# stages_v70.net
KiCad netlist of a schematic drawn in EAGLE
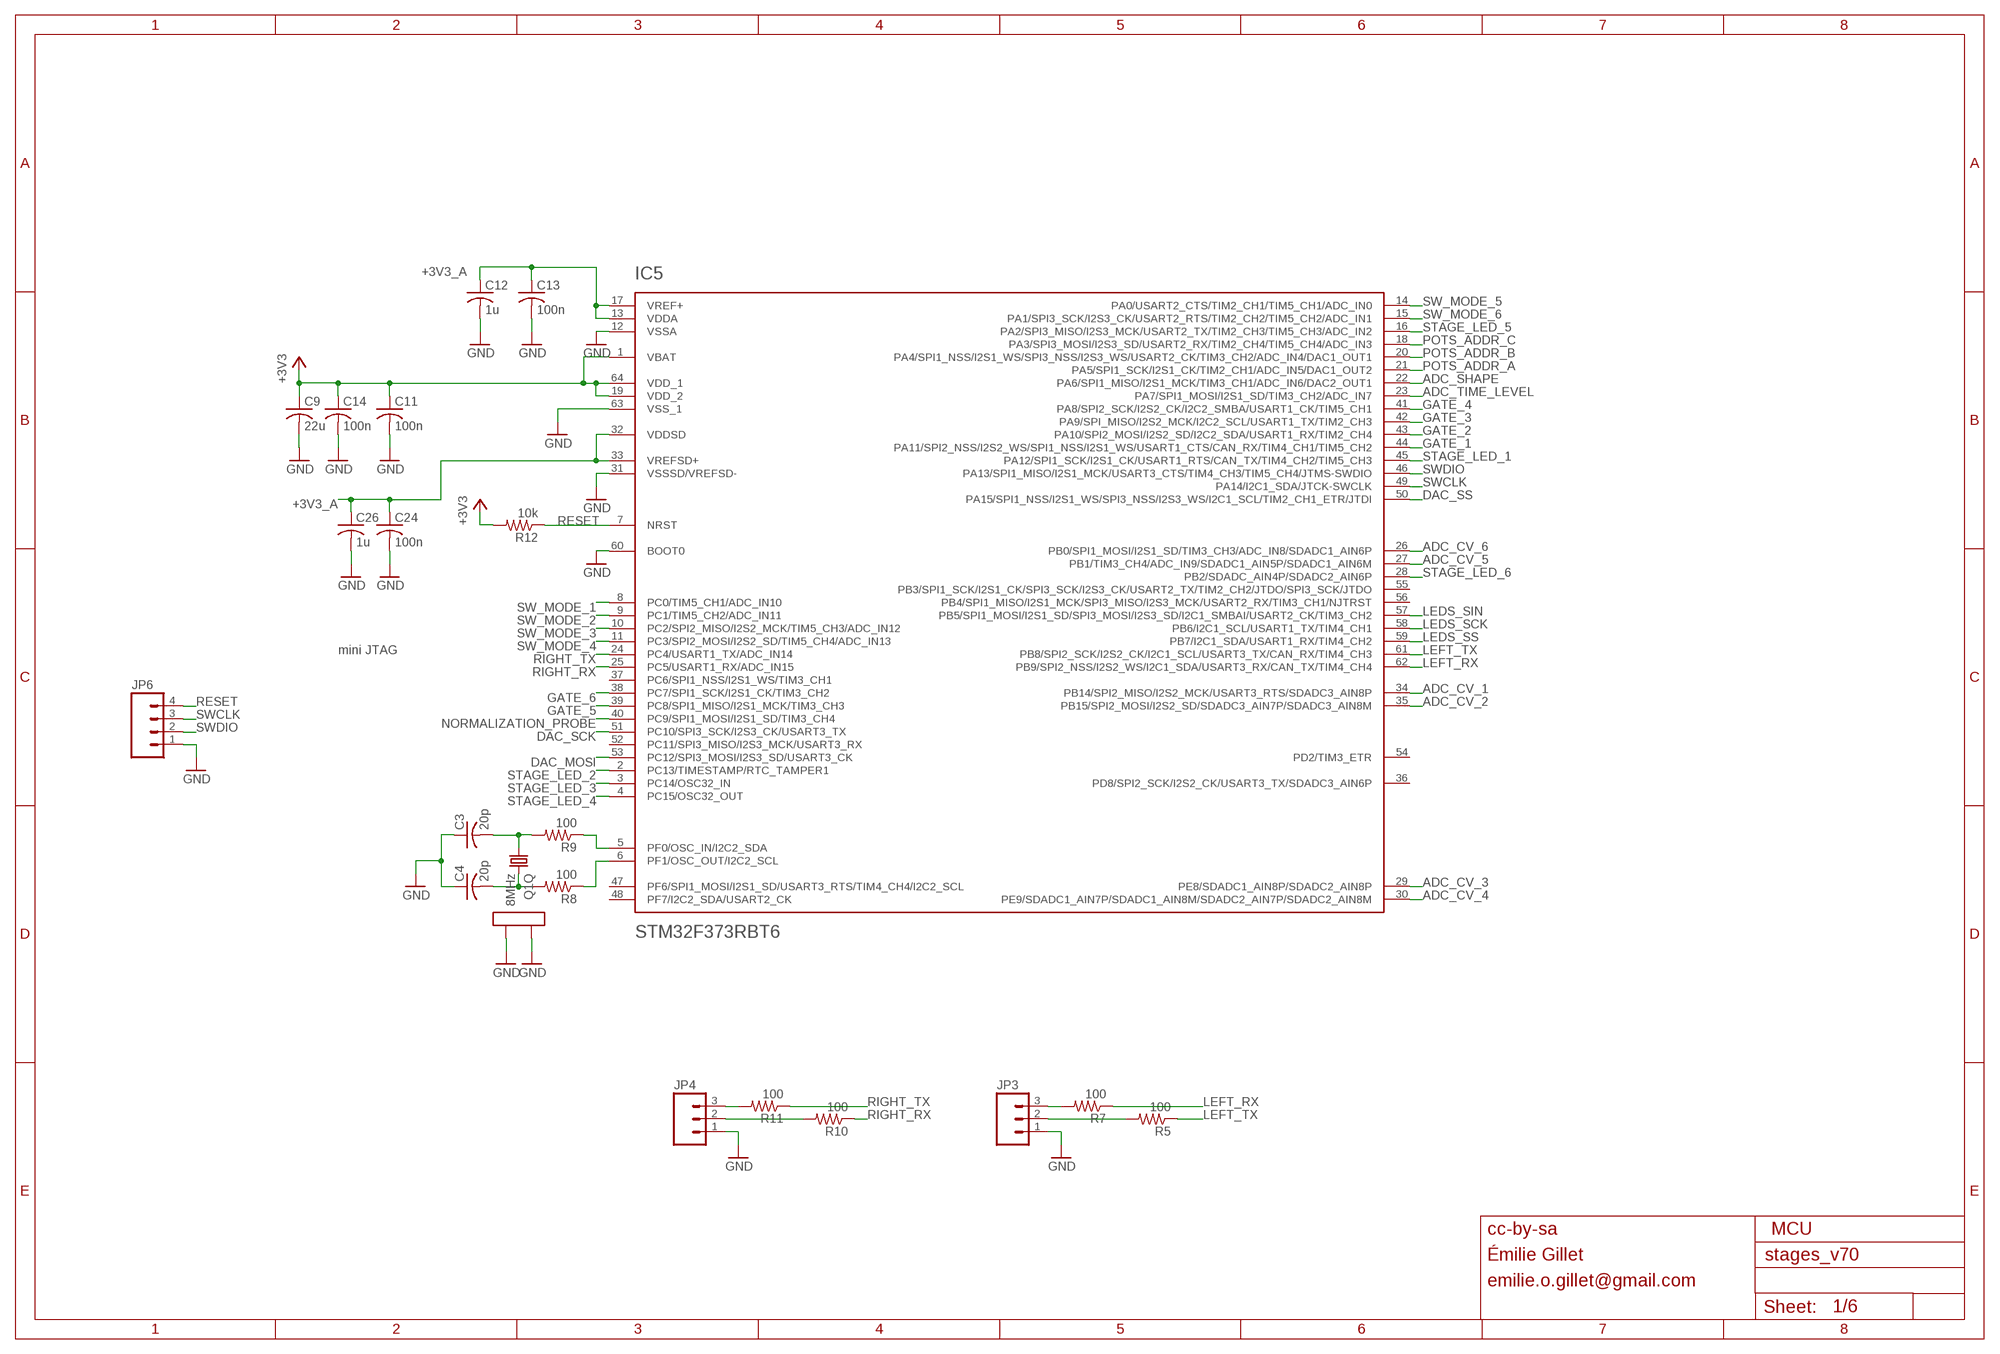
[diagram p0: schematic, sheet 1]
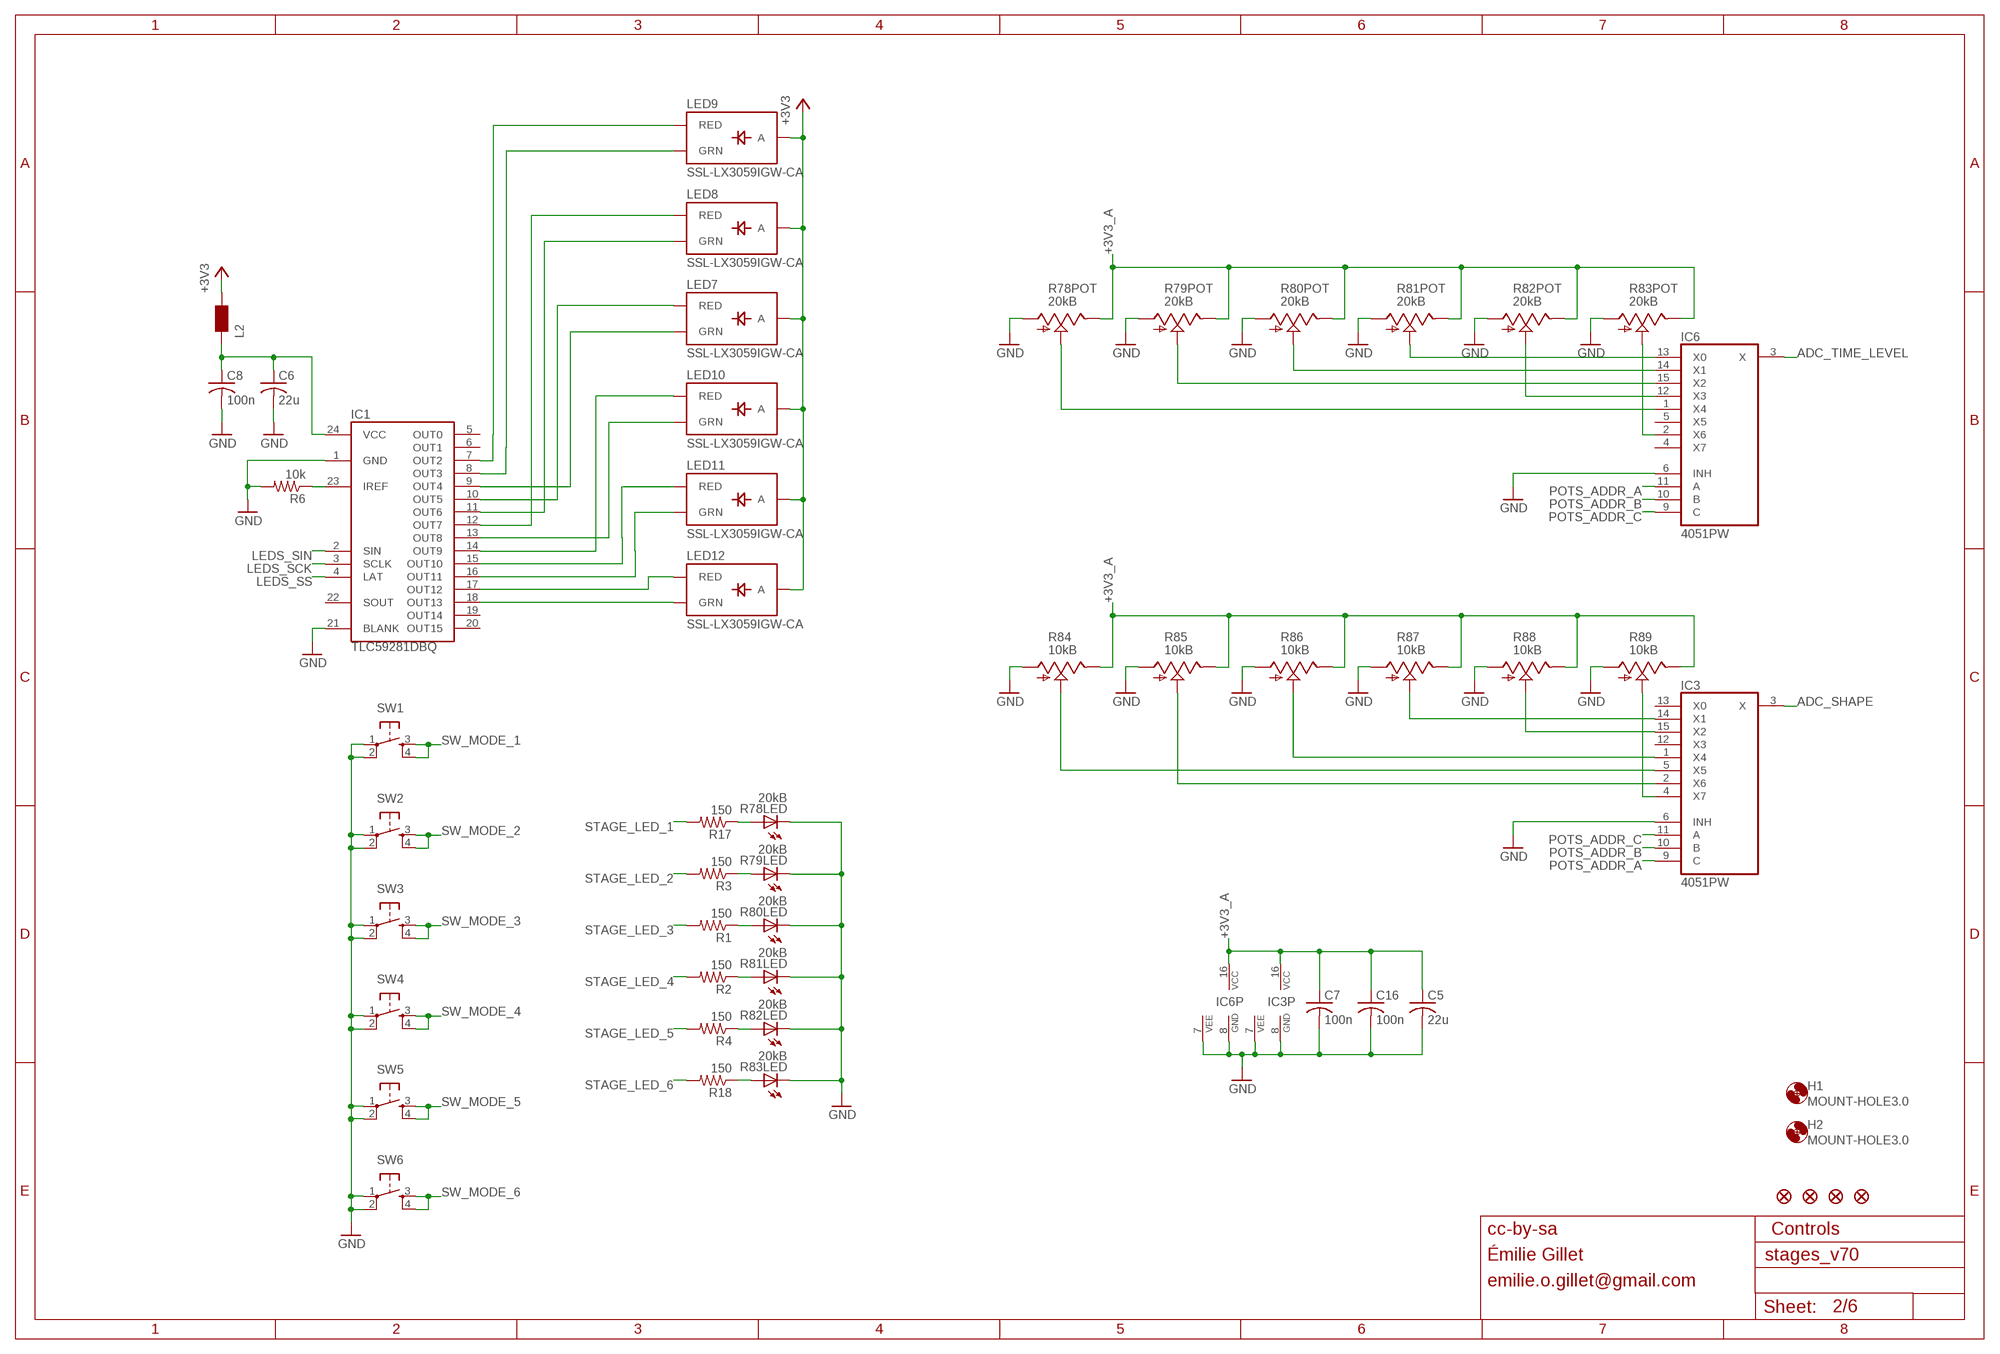
[diagram p1: schematic, sheet 2]
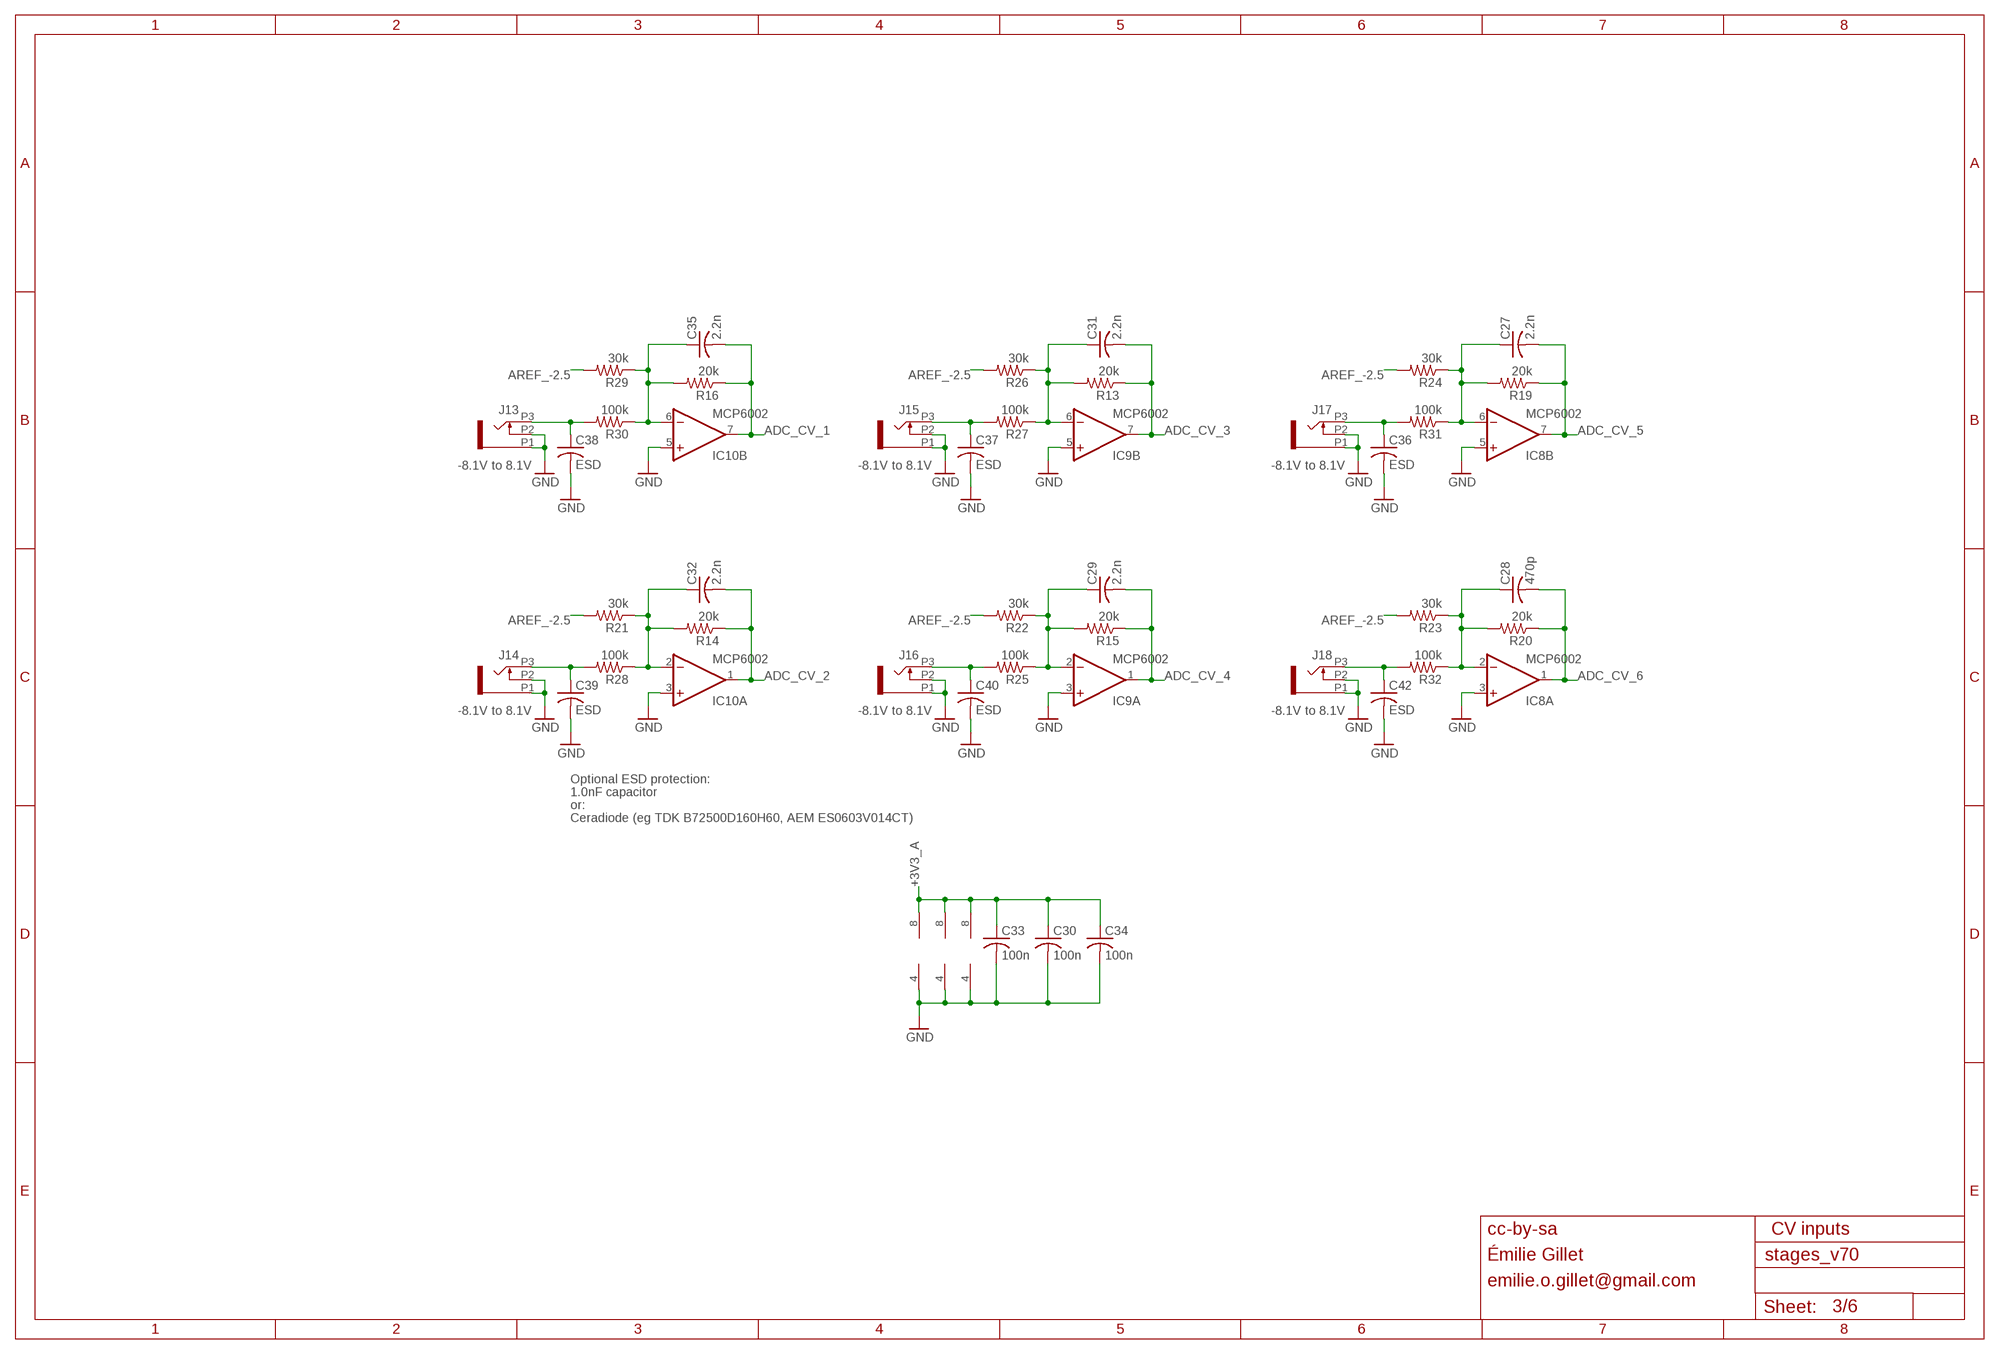
[diagram p2: schematic, sheet 3]
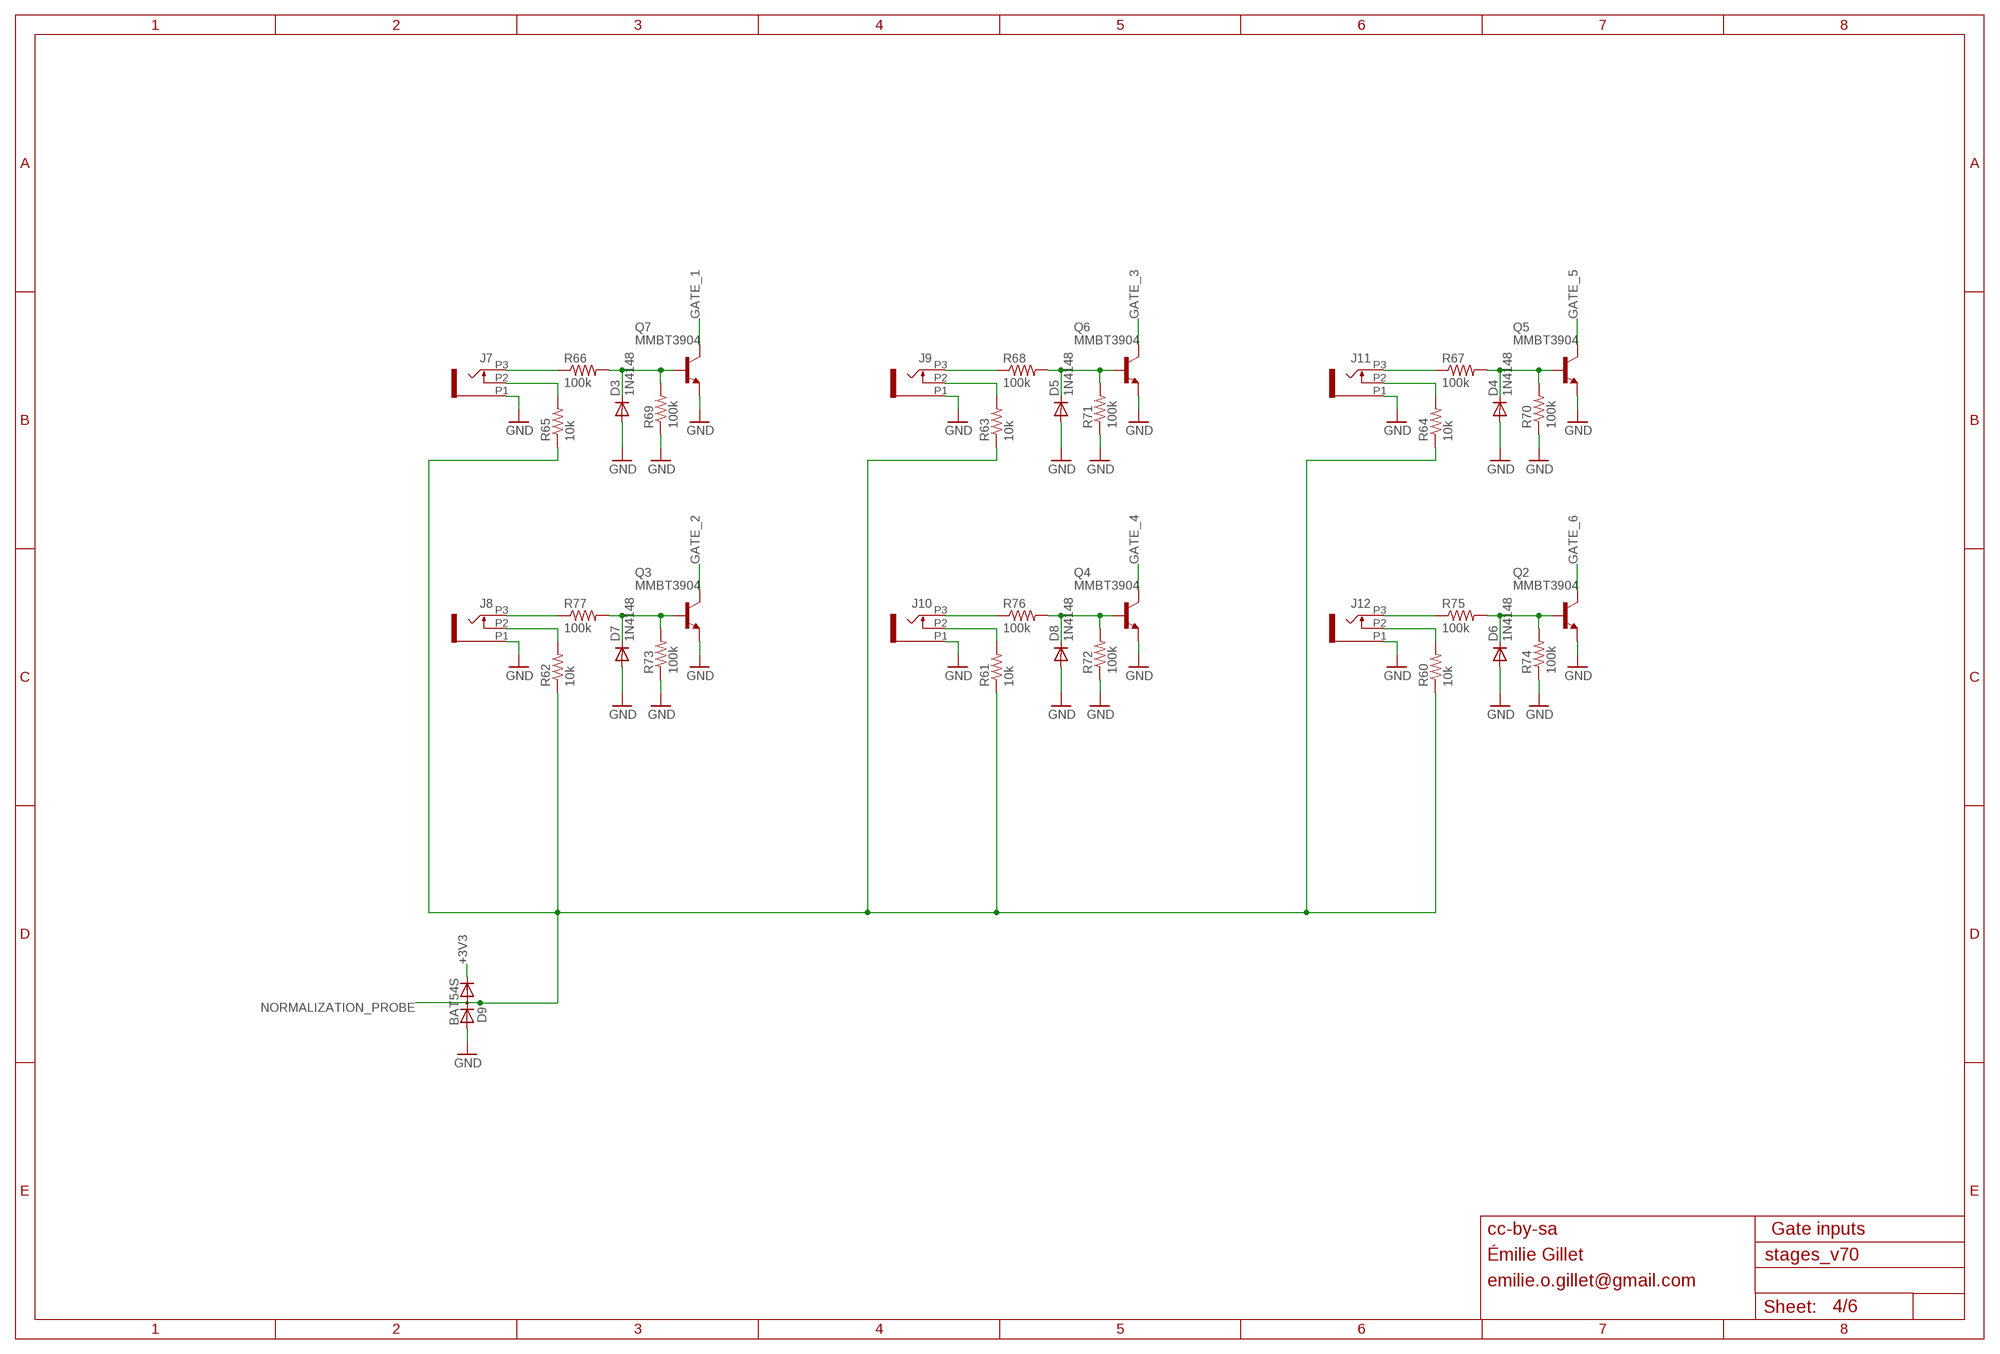
[diagram p3: schematic, sheet 4]
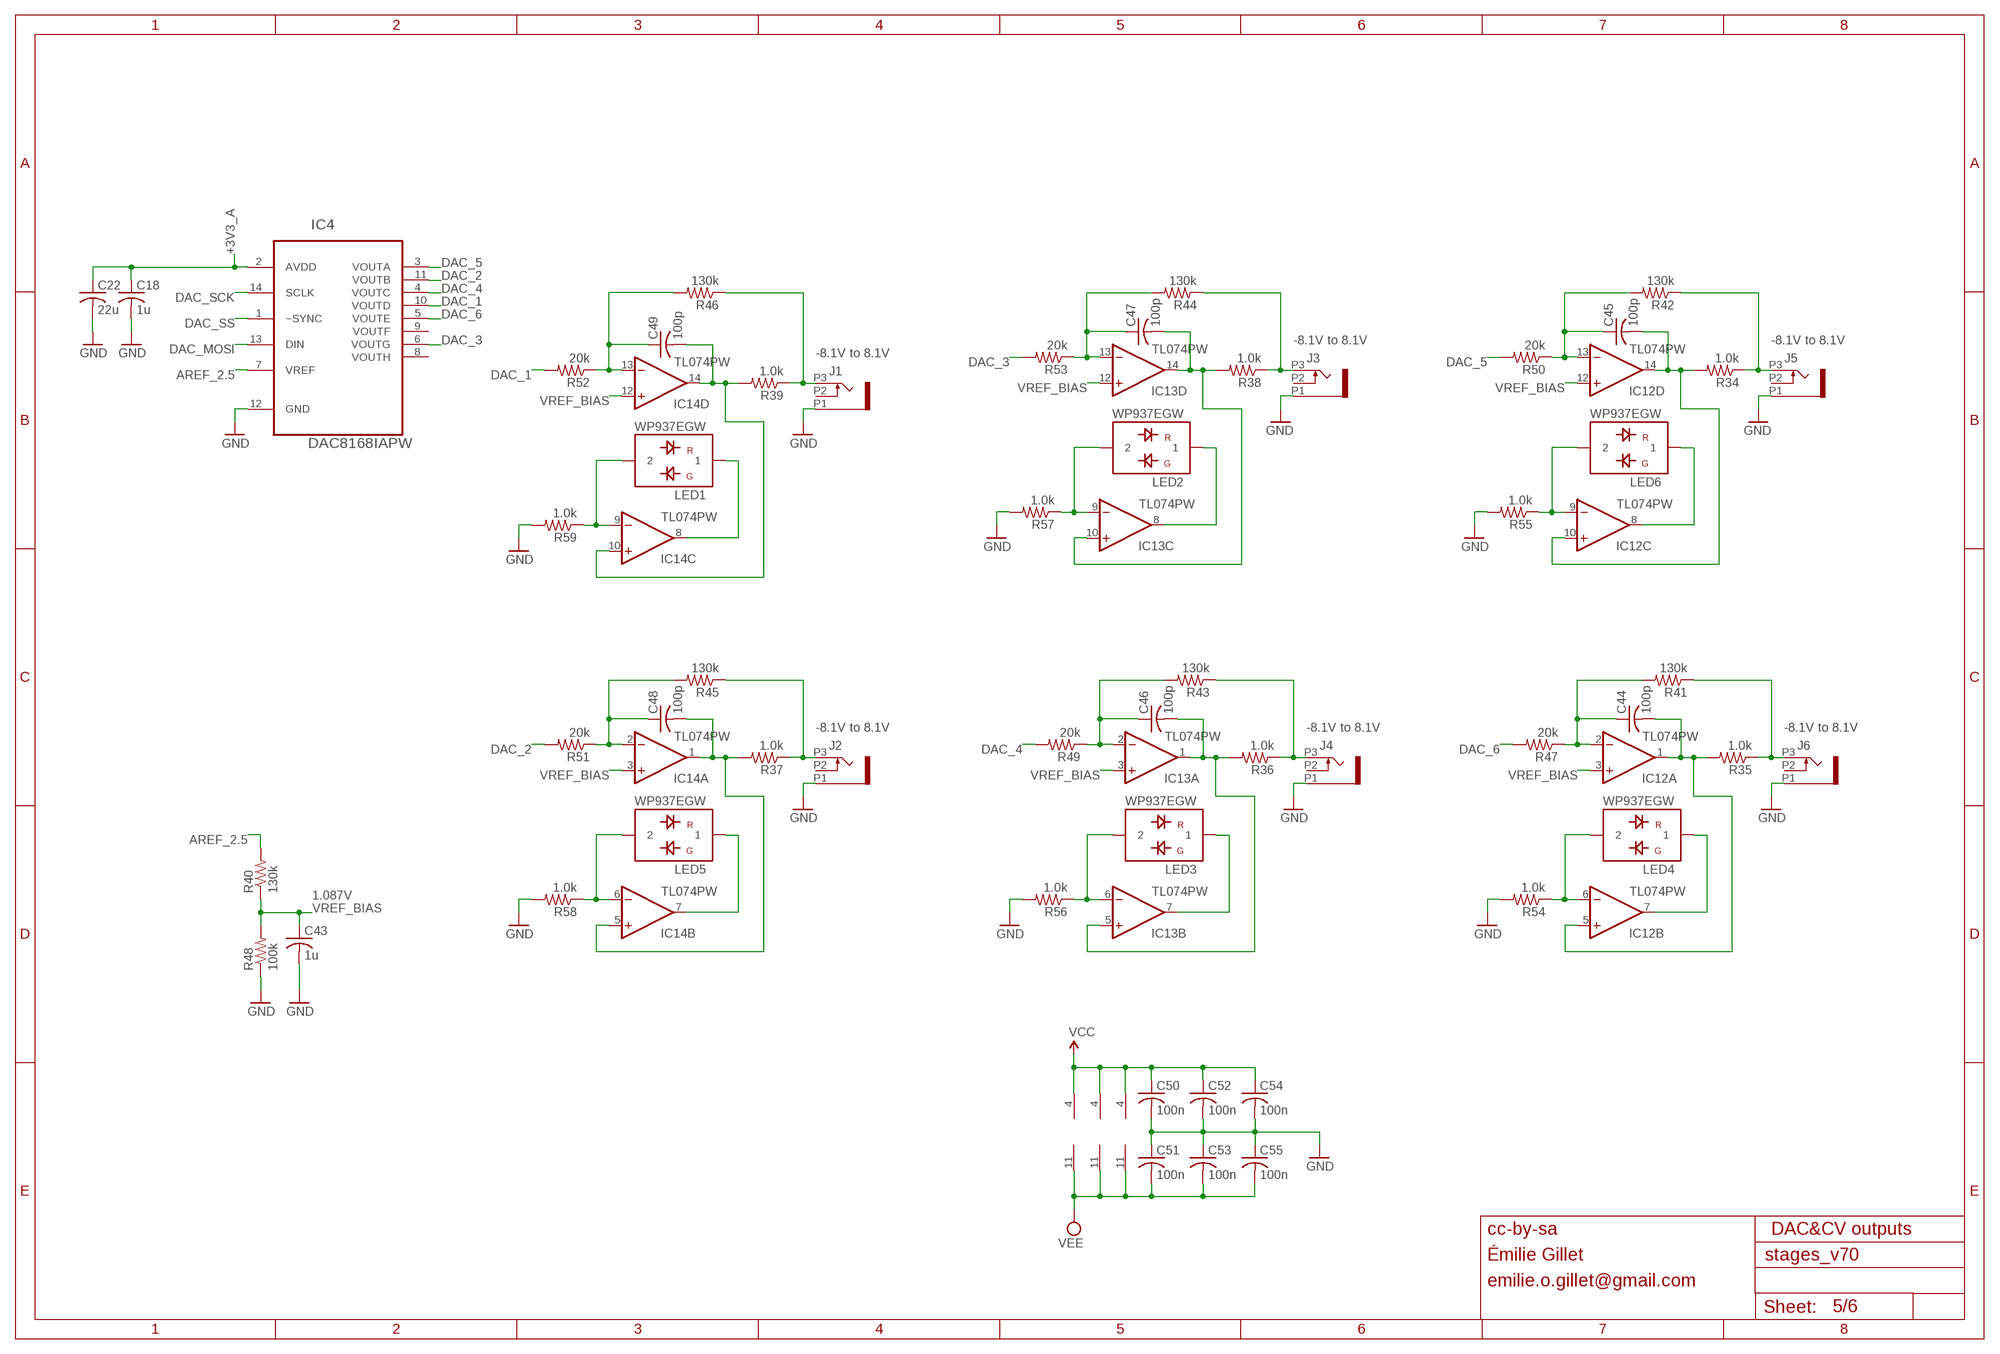
[diagram p4: schematic, sheet 5]
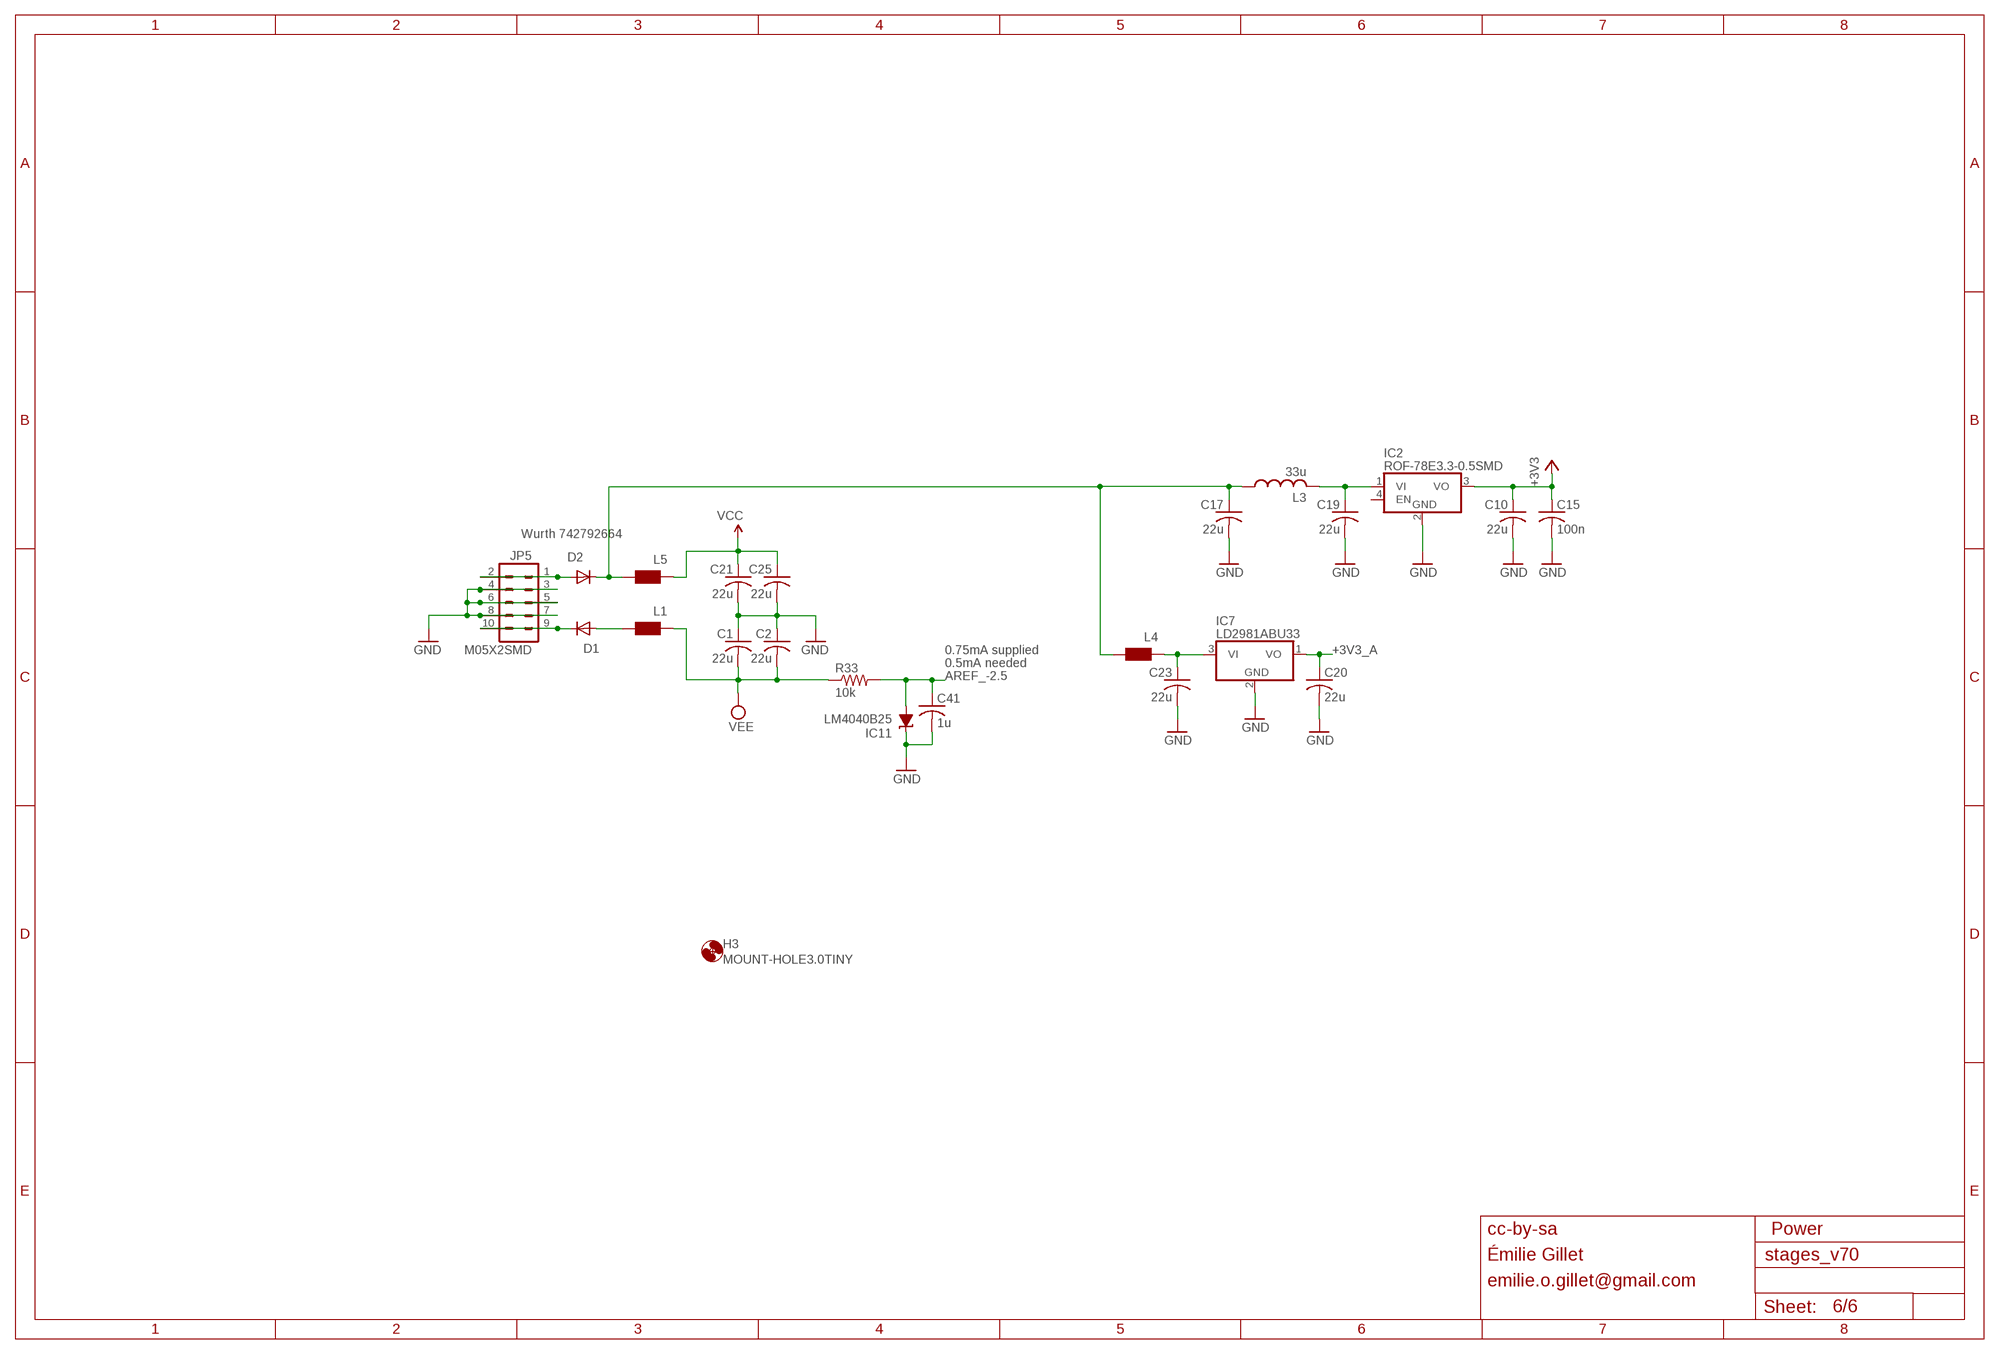
[diagram p5: schematic, sheet 6]

(export (version "E")
  (design (tool "Eeschema 10.0.6"))
  (components
    (comp (ref "C27")
      (value "2.2n")
      (footprint "eagle-import:C0402")
      (libsource (lib "eagle-import") (part "C-USC0402"))
    )
    (comp (ref "C28")
      (value "470p")
      (footprint "eagle-import:C0402")
      (libsource (lib "eagle-import") (part "C-USC0402"))
    )
    (comp (ref "C29")
      (value "2.2n")
      (footprint "eagle-import:C0402")
      (libsource (lib "eagle-import") (part "C-USC0402"))
    )
    (comp (ref "C30")
      (value "100n")
      (footprint "eagle-import:C0402")
      (libsource (lib "eagle-import") (part "C-USC0402"))
    )
    (comp (ref "C31")
      (value "2.2n")
      (footprint "eagle-import:C0402")
      (libsource (lib "eagle-import") (part "C-USC0402"))
    )
    (comp (ref "C32")
      (value "2.2n")
      (footprint "eagle-import:C0402")
      (libsource (lib "eagle-import") (part "C-USC0402"))
    )
    (comp (ref "C33")
      (value "100n")
      (footprint "eagle-import:C0402")
      (libsource (lib "eagle-import") (part "C-USC0402"))
    )
    (comp (ref "C34")
      (value "100n")
      (footprint "eagle-import:C0402")
      (libsource (lib "eagle-import") (part "C-USC0402"))
    )
    (comp (ref "C35")
      (value "2.2n")
      (footprint "eagle-import:C0402")
      (libsource (lib "eagle-import") (part "C-USC0402"))
    )
    (comp (ref "C36")
      (value "ESD")
      (footprint "eagle-import:C0603")
      (libsource (lib "eagle-import") (part "C-USC0603"))
    )
    (comp (ref "C37")
      (value "ESD")
      (footprint "eagle-import:C0603")
      (libsource (lib "eagle-import") (part "C-USC0603"))
    )
    (comp (ref "C38")
      (value "ESD")
      (footprint "eagle-import:C0603")
      (libsource (lib "eagle-import") (part "C-USC0603"))
    )
    (comp (ref "C39")
      (value "ESD")
      (footprint "eagle-import:C0603")
      (libsource (lib "eagle-import") (part "C-USC0603"))
    )
    (comp (ref "C40")
      (value "ESD")
      (footprint "eagle-import:C0603")
      (libsource (lib "eagle-import") (part "C-USC0603"))
    )
    (comp (ref "C42")
      (value "ESD")
      (footprint "eagle-import:C0603")
      (libsource (lib "eagle-import") (part "C-USC0603"))
    )
    (comp (ref "IC8")
      (value "MCP6002")
      (footprint "eagle-import:MSOP-8")
      (libsource (lib "eagle-import") (part "OPA1652DGK"))
    )
    (comp (ref "IC9")
      (value "MCP6002")
      (footprint "eagle-import:MSOP-8")
      (libsource (lib "eagle-import") (part "OPA1652DGK"))
    )
    (comp (ref "IC10")
      (value "MCP6002")
      (footprint "eagle-import:MSOP-8")
      (libsource (lib "eagle-import") (part "OPA1652DGK"))
    )
    (comp (ref "J13")
      (value "PJ301_THONKICONN6")
      (footprint "eagle-import:WQP_PJ_301M6")
      (libsource (lib "eagle-import") (part "PJ301_THONKICONN6"))
    )
    (comp (ref "J14")
      (value "PJ301_THONKICONN6")
      (footprint "eagle-import:WQP_PJ_301M6")
      (libsource (lib "eagle-import") (part "PJ301_THONKICONN6"))
    )
    (comp (ref "J15")
      (value "PJ301_THONKICONN6")
      (footprint "eagle-import:WQP_PJ_301M6")
      (libsource (lib "eagle-import") (part "PJ301_THONKICONN6"))
    )
    (comp (ref "J16")
      (value "PJ301_THONKICONN6")
      (footprint "eagle-import:WQP_PJ_301M6")
      (libsource (lib "eagle-import") (part "PJ301_THONKICONN6"))
    )
    (comp (ref "J17")
      (value "PJ301_THONKICONN6")
      (footprint "eagle-import:WQP_PJ_301M6")
      (libsource (lib "eagle-import") (part "PJ301_THONKICONN6"))
    )
    (comp (ref "J18")
      (value "PJ301_THONKICONN6")
      (footprint "eagle-import:WQP_PJ_301M6")
      (libsource (lib "eagle-import") (part "PJ301_THONKICONN6"))
    )
    (comp (ref "R13")
      (value "20k")
      (footprint "eagle-import:R0402")
      (libsource (lib "eagle-import") (part "R-US_R0402"))
    )
    (comp (ref "R14")
      (value "20k")
      (footprint "eagle-import:R0402")
      (libsource (lib "eagle-import") (part "R-US_R0402"))
    )
    (comp (ref "R15")
      (value "20k")
      (footprint "eagle-import:R0402")
      (libsource (lib "eagle-import") (part "R-US_R0402"))
    )
    (comp (ref "R16")
      (value "20k")
      (footprint "eagle-import:R0402")
      (libsource (lib "eagle-import") (part "R-US_R0402"))
    )
    (comp (ref "R19")
      (value "20k")
      (footprint "eagle-import:R0402")
      (libsource (lib "eagle-import") (part "R-US_R0402"))
    )
    (comp (ref "R20")
      (value "20k")
      (footprint "eagle-import:R0402")
      (libsource (lib "eagle-import") (part "R-US_R0402"))
    )
    (comp (ref "R21")
      (value "30k")
      (footprint "eagle-import:R0402")
      (libsource (lib "eagle-import") (part "R-US_R0402"))
    )
    (comp (ref "R22")
      (value "30k")
      (footprint "eagle-import:R0402")
      (libsource (lib "eagle-import") (part "R-US_R0402"))
    )
    (comp (ref "R23")
      (value "30k")
      (footprint "eagle-import:R0402")
      (libsource (lib "eagle-import") (part "R-US_R0402"))
    )
    (comp (ref "R24")
      (value "30k")
      (footprint "eagle-import:R0402")
      (libsource (lib "eagle-import") (part "R-US_R0402"))
    )
    (comp (ref "R25")
      (value "100k")
      (footprint "eagle-import:R0402")
      (libsource (lib "eagle-import") (part "R-US_R0402"))
    )
    (comp (ref "R26")
      (value "30k")
      (footprint "eagle-import:R0402")
      (libsource (lib "eagle-import") (part "R-US_R0402"))
    )
    (comp (ref "R27")
      (value "100k")
      (footprint "eagle-import:R0402")
      (libsource (lib "eagle-import") (part "R-US_R0402"))
    )
    (comp (ref "R28")
      (value "100k")
      (footprint "eagle-import:R0402")
      (libsource (lib "eagle-import") (part "R-US_R0402"))
    )
    (comp (ref "R29")
      (value "30k")
      (footprint "eagle-import:R0402")
      (libsource (lib "eagle-import") (part "R-US_R0402"))
    )
    (comp (ref "R30")
      (value "100k")
      (footprint "eagle-import:R0402")
      (libsource (lib "eagle-import") (part "R-US_R0402"))
    )
    (comp (ref "R31")
      (value "100k")
      (footprint "eagle-import:R0402")
      (libsource (lib "eagle-import") (part "R-US_R0402"))
    )
    (comp (ref "R32")
      (value "100k")
      (footprint "eagle-import:R0402")
      (libsource (lib "eagle-import") (part "R-US_R0402"))
    )
    (comp (ref "C5")
      (value "22u")
      (footprint "eagle-import:C1206")
      (libsource (lib "eagle-import") (part "C-USC1206"))
    )
    (comp (ref "C6")
      (value "22u")
      (footprint "eagle-import:C1206")
      (libsource (lib "eagle-import") (part "C-USC1206"))
    )
    (comp (ref "C7")
      (value "100n")
      (footprint "eagle-import:C0402")
      (libsource (lib "eagle-import") (part "C-USC0402"))
    )
    (comp (ref "C8")
      (value "100n")
      (footprint "eagle-import:C0402")
      (libsource (lib "eagle-import") (part "C-USC0402"))
    )
    (comp (ref "C16")
      (value "100n")
      (footprint "eagle-import:C0402")
      (libsource (lib "eagle-import") (part "C-USC0402"))
    )
    (comp (ref "H1")
      (value "MOUNT-HOLE3.0")
      (footprint "eagle-import:3,0")
      (libsource (lib "eagle-import") (part "MOUNT-HOLE3.0"))
    )
    (comp (ref "H2")
      (value "MOUNT-HOLE3.0")
      (footprint "eagle-import:3,0")
      (libsource (lib "eagle-import") (part "MOUNT-HOLE3.0"))
    )
    (comp (ref "IC1")
      (value "TLC59281DBQ")
      (footprint "eagle-import:TSSOP24_0635")
      (libsource (lib "eagle-import") (part "TLC59281DBQ"))
    )
    (comp (ref "IC3")
      (value "4051PW")
      (footprint "eagle-import:TSSOP16_065")
      (libsource (lib "eagle-import") (part "4051PW"))
    )
    (comp (ref "IC6")
      (value "4051PW")
      (footprint "eagle-import:TSSOP16_065")
      (libsource (lib "eagle-import") (part "4051PW"))
    )
    (comp (ref "JP1")
      (value "FIDUCIAL1X2")
      (footprint "eagle-import:FIDUCIAL-1X2")
      (libsource (lib "eagle-import") (part "FIDUCIAL1X2"))
    )
    (comp (ref "JP2")
      (value "FIDUCIAL1X2")
      (footprint "eagle-import:FIDUCIAL-1X2")
      (libsource (lib "eagle-import") (part "FIDUCIAL1X2"))
    )
    (comp (ref "JP7")
      (value "FIDUCIAL1X2")
      (footprint "eagle-import:FIDUCIAL-1X2")
      (libsource (lib "eagle-import") (part "FIDUCIAL1X2"))
    )
    (comp (ref "JP8")
      (value "FIDUCIAL1X2")
      (footprint "eagle-import:FIDUCIAL-1X2")
      (libsource (lib "eagle-import") (part "FIDUCIAL1X2"))
    )
    (comp (ref "L2")
      (value "WE-CBF_0603")
      (footprint "eagle-import:0603")
      (libsource (lib "eagle-import") (part "WE-CBF_0603"))
    )
    (comp (ref "LED7")
      (value "SSL-LX3059IGW-CA")
      (footprint "eagle-import:LED-BICOLOR-THROUGHHOLE-LUMEX")
      (libsource (lib "eagle-import") (part "LED-BICOLOR-THROUGHHOLE-CA"))
    )
    (comp (ref "LED8")
      (value "SSL-LX3059IGW-CA")
      (footprint "eagle-import:LED-BICOLOR-THROUGHHOLE-LUMEX")
      (libsource (lib "eagle-import") (part "LED-BICOLOR-THROUGHHOLE-CA"))
    )
    (comp (ref "LED9")
      (value "SSL-LX3059IGW-CA")
      (footprint "eagle-import:LED-BICOLOR-THROUGHHOLE-LUMEX")
      (libsource (lib "eagle-import") (part "LED-BICOLOR-THROUGHHOLE-CA"))
    )
    (comp (ref "LED10")
      (value "SSL-LX3059IGW-CA")
      (footprint "eagle-import:LED-BICOLOR-THROUGHHOLE-LUMEX")
      (libsource (lib "eagle-import") (part "LED-BICOLOR-THROUGHHOLE-CA"))
    )
    (comp (ref "LED11")
      (value "SSL-LX3059IGW-CA")
      (footprint "eagle-import:LED-BICOLOR-THROUGHHOLE-LUMEX")
      (libsource (lib "eagle-import") (part "LED-BICOLOR-THROUGHHOLE-CA"))
    )
    (comp (ref "LED12")
      (value "SSL-LX3059IGW-CA")
      (footprint "eagle-import:LED-BICOLOR-THROUGHHOLE-LUMEX")
      (libsource (lib "eagle-import") (part "LED-BICOLOR-THROUGHHOLE-CA"))
    )
    (comp (ref "R1")
      (value "150")
      (footprint "eagle-import:R0402")
      (libsource (lib "eagle-import") (part "R-US_R0402"))
    )
    (comp (ref "R2")
      (value "150")
      (footprint "eagle-import:R0402")
      (libsource (lib "eagle-import") (part "R-US_R0402"))
    )
    (comp (ref "R3")
      (value "150")
      (footprint "eagle-import:R0402")
      (libsource (lib "eagle-import") (part "R-US_R0402"))
    )
    (comp (ref "R4")
      (value "150")
      (footprint "eagle-import:R0402")
      (libsource (lib "eagle-import") (part "R-US_R0402"))
    )
    (comp (ref "R6")
      (value "10k")
      (footprint "eagle-import:R0402")
      (libsource (lib "eagle-import") (part "R-US_R0402"))
    )
    (comp (ref "R17")
      (value "150")
      (footprint "eagle-import:R0402")
      (libsource (lib "eagle-import") (part "R-US_R0402"))
    )
    (comp (ref "R18")
      (value "150")
      (footprint "eagle-import:R0402")
      (libsource (lib "eagle-import") (part "R-US_R0402"))
    )
    (comp (ref "R78")
      (value "20kB")
      (footprint "eagle-import:BOURNS_SLIDER")
      (libsource (lib "eagle-import") (part "BOURNS_SLIDER"))
    )
    (comp (ref "R79")
      (value "20kB")
      (footprint "eagle-import:BOURNS_SLIDER")
      (libsource (lib "eagle-import") (part "BOURNS_SLIDER"))
    )
    (comp (ref "R80")
      (value "20kB")
      (footprint "eagle-import:BOURNS_SLIDER")
      (libsource (lib "eagle-import") (part "BOURNS_SLIDER"))
    )
    (comp (ref "R81")
      (value "20kB")
      (footprint "eagle-import:BOURNS_SLIDER")
      (libsource (lib "eagle-import") (part "BOURNS_SLIDER"))
    )
    (comp (ref "R82")
      (value "20kB")
      (footprint "eagle-import:BOURNS_SLIDER")
      (libsource (lib "eagle-import") (part "BOURNS_SLIDER"))
    )
    (comp (ref "R83")
      (value "20kB")
      (footprint "eagle-import:BOURNS_SLIDER")
      (libsource (lib "eagle-import") (part "BOURNS_SLIDER"))
    )
    (comp (ref "R84")
      (value "10kB")
      (footprint "eagle-import:ALPS_POT_NARROW")
      (libsource (lib "eagle-import") (part "POT_USVERTICAL_NARROW"))
    )
    (comp (ref "R85")
      (value "10kB")
      (footprint "eagle-import:ALPS_POT_NARROW")
      (libsource (lib "eagle-import") (part "POT_USVERTICAL_NARROW"))
    )
    (comp (ref "R86")
      (value "10kB")
      (footprint "eagle-import:ALPS_POT_NARROW")
      (libsource (lib "eagle-import") (part "POT_USVERTICAL_NARROW"))
    )
    (comp (ref "R87")
      (value "10kB")
      (footprint "eagle-import:ALPS_POT_NARROW")
      (libsource (lib "eagle-import") (part "POT_USVERTICAL_NARROW"))
    )
    (comp (ref "R88")
      (value "10kB")
      (footprint "eagle-import:ALPS_POT_NARROW")
      (libsource (lib "eagle-import") (part "POT_USVERTICAL_NARROW"))
    )
    (comp (ref "R89")
      (value "10kB")
      (footprint "eagle-import:ALPS_POT_NARROW")
      (libsource (lib "eagle-import") (part "POT_USVERTICAL_NARROW"))
    )
    (comp (ref "SW1")
      (value "TAC_SWITCHPTH")
      (footprint "eagle-import:TACTILE-PTH")
      (libsource (lib "eagle-import") (part "TAC_SWITCHPTH"))
    )
    (comp (ref "SW2")
      (value "TAC_SWITCHPTH")
      (footprint "eagle-import:TACTILE-PTH")
      (libsource (lib "eagle-import") (part "TAC_SWITCHPTH"))
    )
    (comp (ref "SW3")
      (value "TAC_SWITCHPTH")
      (footprint "eagle-import:TACTILE-PTH")
      (libsource (lib "eagle-import") (part "TAC_SWITCHPTH"))
    )
    (comp (ref "SW4")
      (value "TAC_SWITCHPTH")
      (footprint "eagle-import:TACTILE-PTH")
      (libsource (lib "eagle-import") (part "TAC_SWITCHPTH"))
    )
    (comp (ref "SW5")
      (value "TAC_SWITCHPTH")
      (footprint "eagle-import:TACTILE-PTH")
      (libsource (lib "eagle-import") (part "TAC_SWITCHPTH"))
    )
    (comp (ref "SW6")
      (value "TAC_SWITCHPTH")
      (footprint "eagle-import:TACTILE-PTH")
      (libsource (lib "eagle-import") (part "TAC_SWITCHPTH"))
    )
    (comp (ref "C3")
      (value "20p")
      (footprint "eagle-import:C0402")
      (libsource (lib "eagle-import") (part "C-USC0402"))
    )
    (comp (ref "C4")
      (value "20p")
      (footprint "eagle-import:C0402")
      (libsource (lib "eagle-import") (part "C-USC0402"))
    )
    (comp (ref "C9")
      (value "22u")
      (footprint "eagle-import:C1206")
      (libsource (lib "eagle-import") (part "C-USC1206"))
    )
    (comp (ref "C11")
      (value "100n")
      (footprint "eagle-import:C0402")
      (libsource (lib "eagle-import") (part "C-USC0402"))
    )
    (comp (ref "C12")
      (value "1u")
      (footprint "eagle-import:C0402")
      (libsource (lib "eagle-import") (part "C-USC0402"))
    )
    (comp (ref "C13")
      (value "100n")
      (footprint "eagle-import:C0402")
      (libsource (lib "eagle-import") (part "C-USC0402"))
    )
    (comp (ref "C14")
      (value "100n")
      (footprint "eagle-import:C0402")
      (libsource (lib "eagle-import") (part "C-USC0402"))
    )
    (comp (ref "C24")
      (value "100n")
      (footprint "eagle-import:C0402")
      (libsource (lib "eagle-import") (part "C-USC0402"))
    )
    (comp (ref "C26")
      (value "1u")
      (footprint "eagle-import:C0402")
      (libsource (lib "eagle-import") (part "C-USC0402"))
    )
    (comp (ref "IC5")
      (value "STM32F373RBT6")
      (footprint "eagle-import:TQFP-10X10-64")
      (libsource (lib "eagle-import") (part "STM32F373R"))
    )
    (comp (ref "JP3")
      (value "M03PTH")
      (footprint "eagle-import:1X03")
      (libsource (lib "eagle-import") (part "M03PTH"))
    )
    (comp (ref "JP4")
      (value "M03PTH")
      (footprint "eagle-import:1X03")
      (libsource (lib "eagle-import") (part "M03PTH"))
    )
    (comp (ref "JP6")
      (value "M04PTH")
      (footprint "eagle-import:1X04")
      (libsource (lib "eagle-import") (part "M04PTH"))
    )
    (comp (ref "Q1")
      (value "8MHz")
      (footprint "eagle-import:CTS406")
      (libsource (lib "eagle-import") (part "CRYSTAL"))
    )
    (comp (ref "R5")
      (value "100")
      (footprint "eagle-import:R0402")
      (libsource (lib "eagle-import") (part "R-US_R0402"))
    )
    (comp (ref "R7")
      (value "100")
      (footprint "eagle-import:R0402")
      (libsource (lib "eagle-import") (part "R-US_R0402"))
    )
    (comp (ref "R8")
      (value "100")
      (footprint "eagle-import:R0402")
      (libsource (lib "eagle-import") (part "R-US_R0402"))
    )
    (comp (ref "R9")
      (value "100")
      (footprint "eagle-import:R0402")
      (libsource (lib "eagle-import") (part "R-US_R0402"))
    )
    (comp (ref "R10")
      (value "100")
      (footprint "eagle-import:R0402")
      (libsource (lib "eagle-import") (part "R-US_R0402"))
    )
    (comp (ref "R11")
      (value "100")
      (footprint "eagle-import:R0402")
      (libsource (lib "eagle-import") (part "R-US_R0402"))
    )
    (comp (ref "R12")
      (value "10k")
      (footprint "eagle-import:R0402")
      (libsource (lib "eagle-import") (part "R-US_R0402"))
    )
    (comp (ref "C18")
      (value "1u")
      (footprint "eagle-import:C0402")
      (libsource (lib "eagle-import") (part "C-USC0402"))
    )
    (comp (ref "C22")
      (value "22u")
      (footprint "eagle-import:C1206")
      (libsource (lib "eagle-import") (part "C-USC1206"))
    )
    (comp (ref "C43")
      (value "1u")
      (footprint "eagle-import:C0402")
      (libsource (lib "eagle-import") (part "C-USC0402"))
    )
    (comp (ref "C44")
      (value "100p")
      (footprint "eagle-import:C0402")
      (libsource (lib "eagle-import") (part "C-USC0402"))
    )
    (comp (ref "C45")
      (value "100p")
      (footprint "eagle-import:C0402")
      (libsource (lib "eagle-import") (part "C-USC0402"))
    )
    (comp (ref "C46")
      (value "100p")
      (footprint "eagle-import:C0402")
      (libsource (lib "eagle-import") (part "C-USC0402"))
    )
    (comp (ref "C47")
      (value "100p")
      (footprint "eagle-import:C0402")
      (libsource (lib "eagle-import") (part "C-USC0402"))
    )
    (comp (ref "C48")
      (value "100p")
      (footprint "eagle-import:C0402")
      (libsource (lib "eagle-import") (part "C-USC0402"))
    )
    (comp (ref "C49")
      (value "100p")
      (footprint "eagle-import:C0402")
      (libsource (lib "eagle-import") (part "C-USC0402"))
    )
    (comp (ref "C50")
      (value "100n")
      (footprint "eagle-import:C0402")
      (libsource (lib "eagle-import") (part "C-USC0402"))
    )
    (comp (ref "C51")
      (value "100n")
      (footprint "eagle-import:C0402")
      (libsource (lib "eagle-import") (part "C-USC0402"))
    )
    (comp (ref "C52")
      (value "100n")
      (footprint "eagle-import:C0402")
      (libsource (lib "eagle-import") (part "C-USC0402"))
    )
    (comp (ref "C53")
      (value "100n")
      (footprint "eagle-import:C0402")
      (libsource (lib "eagle-import") (part "C-USC0402"))
    )
    (comp (ref "C54")
      (value "100n")
      (footprint "eagle-import:C0402")
      (libsource (lib "eagle-import") (part "C-USC0402"))
    )
    (comp (ref "C55")
      (value "100n")
      (footprint "eagle-import:C0402")
      (libsource (lib "eagle-import") (part "C-USC0402"))
    )
    (comp (ref "IC4")
      (value "DAC8168IAPW")
      (footprint "eagle-import:RPDSOG14")
      (libsource (lib "eagle-import") (part "DAC8168PW"))
    )
    (comp (ref "IC12")
      (value "TL074PW")
      (footprint "eagle-import:TSSOP14_065")
      (libsource (lib "eagle-import") (part "TL074PW"))
    )
    (comp (ref "IC13")
      (value "TL074PW")
      (footprint "eagle-import:TSSOP14_065")
      (libsource (lib "eagle-import") (part "TL074PW"))
    )
    (comp (ref "IC14")
      (value "TL074PW")
      (footprint "eagle-import:TSSOP14_065")
      (libsource (lib "eagle-import") (part "TL074PW"))
    )
    (comp (ref "J1")
      (value "PJ301_THONKICONN6")
      (footprint "eagle-import:WQP_PJ_301M6")
      (libsource (lib "eagle-import") (part "PJ301_THONKICONN6"))
    )
    (comp (ref "J2")
      (value "PJ301_THONKICONN6")
      (footprint "eagle-import:WQP_PJ_301M6")
      (libsource (lib "eagle-import") (part "PJ301_THONKICONN6"))
    )
    (comp (ref "J3")
      (value "PJ301_THONKICONN6")
      (footprint "eagle-import:WQP_PJ_301M6")
      (libsource (lib "eagle-import") (part "PJ301_THONKICONN6"))
    )
    (comp (ref "J4")
      (value "PJ301_THONKICONN6")
      (footprint "eagle-import:WQP_PJ_301M6")
      (libsource (lib "eagle-import") (part "PJ301_THONKICONN6"))
    )
    (comp (ref "J5")
      (value "PJ301_THONKICONN6")
      (footprint "eagle-import:WQP_PJ_301M6")
      (libsource (lib "eagle-import") (part "PJ301_THONKICONN6"))
    )
    (comp (ref "J6")
      (value "PJ301_THONKICONN6")
      (footprint "eagle-import:WQP_PJ_301M6")
      (libsource (lib "eagle-import") (part "PJ301_THONKICONN6"))
    )
    (comp (ref "LED1")
      (value "WP937EGW")
      (footprint "eagle-import:LED3MM")
      (libsource (lib "eagle-import") (part "LED-BICOLOR-SHARED-THROUGHHOLE"))
    )
    (comp (ref "LED2")
      (value "WP937EGW")
      (footprint "eagle-import:LED3MM")
      (libsource (lib "eagle-import") (part "LED-BICOLOR-SHARED-THROUGHHOLE"))
    )
    (comp (ref "LED3")
      (value "WP937EGW")
      (footprint "eagle-import:LED3MM")
      (libsource (lib "eagle-import") (part "LED-BICOLOR-SHARED-THROUGHHOLE"))
    )
    (comp (ref "LED4")
      (value "WP937EGW")
      (footprint "eagle-import:LED3MM")
      (libsource (lib "eagle-import") (part "LED-BICOLOR-SHARED-THROUGHHOLE"))
    )
    (comp (ref "LED5")
      (value "WP937EGW")
      (footprint "eagle-import:LED3MM")
      (libsource (lib "eagle-import") (part "LED-BICOLOR-SHARED-THROUGHHOLE"))
    )
    (comp (ref "LED6")
      (value "WP937EGW")
      (footprint "eagle-import:LED3MM")
      (libsource (lib "eagle-import") (part "LED-BICOLOR-SHARED-THROUGHHOLE"))
    )
    (comp (ref "R34")
      (value "1.0k")
      (footprint "eagle-import:R0603")
      (libsource (lib "eagle-import") (part "R-US_R0603"))
    )
    (comp (ref "R35")
      (value "1.0k")
      (footprint "eagle-import:R0603")
      (libsource (lib "eagle-import") (part "R-US_R0603"))
    )
    (comp (ref "R36")
      (value "1.0k")
      (footprint "eagle-import:R0603")
      (libsource (lib "eagle-import") (part "R-US_R0603"))
    )
    (comp (ref "R37")
      (value "1.0k")
      (footprint "eagle-import:R0603")
      (libsource (lib "eagle-import") (part "R-US_R0603"))
    )
    (comp (ref "R38")
      (value "1.0k")
      (footprint "eagle-import:R0603")
      (libsource (lib "eagle-import") (part "R-US_R0603"))
    )
    (comp (ref "R39")
      (value "1.0k")
      (footprint "eagle-import:R0603")
      (libsource (lib "eagle-import") (part "R-US_R0603"))
    )
    (comp (ref "R40")
      (value "130k")
      (footprint "eagle-import:R0402")
      (libsource (lib "eagle-import") (part "R-US_R0402"))
    )
    (comp (ref "R41")
      (value "130k")
      (footprint "eagle-import:R0402")
      (libsource (lib "eagle-import") (part "R-US_R0402"))
    )
    (comp (ref "R42")
      (value "130k")
      (footprint "eagle-import:R0402")
      (libsource (lib "eagle-import") (part "R-US_R0402"))
    )
    (comp (ref "R43")
      (value "130k")
      (footprint "eagle-import:R0402")
      (libsource (lib "eagle-import") (part "R-US_R0402"))
    )
    (comp (ref "R44")
      (value "130k")
      (footprint "eagle-import:R0402")
      (libsource (lib "eagle-import") (part "R-US_R0402"))
    )
    (comp (ref "R45")
      (value "130k")
      (footprint "eagle-import:R0402")
      (libsource (lib "eagle-import") (part "R-US_R0402"))
    )
    (comp (ref "R46")
      (value "130k")
      (footprint "eagle-import:R0402")
      (libsource (lib "eagle-import") (part "R-US_R0402"))
    )
    (comp (ref "R47")
      (value "20k")
      (footprint "eagle-import:R0402")
      (libsource (lib "eagle-import") (part "R-US_R0402"))
    )
    (comp (ref "R48")
      (value "100k")
      (footprint "eagle-import:R0402")
      (libsource (lib "eagle-import") (part "R-US_R0402"))
    )
    (comp (ref "R49")
      (value "20k")
      (footprint "eagle-import:R0402")
      (libsource (lib "eagle-import") (part "R-US_R0402"))
    )
    (comp (ref "R50")
      (value "20k")
      (footprint "eagle-import:R0402")
      (libsource (lib "eagle-import") (part "R-US_R0402"))
    )
    (comp (ref "R51")
      (value "20k")
      (footprint "eagle-import:R0402")
      (libsource (lib "eagle-import") (part "R-US_R0402"))
    )
    (comp (ref "R52")
      (value "20k")
      (footprint "eagle-import:R0402")
      (libsource (lib "eagle-import") (part "R-US_R0402"))
    )
    (comp (ref "R53")
      (value "20k")
      (footprint "eagle-import:R0402")
      (libsource (lib "eagle-import") (part "R-US_R0402"))
    )
    (comp (ref "R54")
      (value "1.0k")
      (footprint "eagle-import:R0402")
      (libsource (lib "eagle-import") (part "R-US_R0402"))
    )
    (comp (ref "R55")
      (value "1.0k")
      (footprint "eagle-import:R0402")
      (libsource (lib "eagle-import") (part "R-US_R0402"))
    )
    (comp (ref "R56")
      (value "1.0k")
      (footprint "eagle-import:R0402")
      (libsource (lib "eagle-import") (part "R-US_R0402"))
    )
    (comp (ref "R57")
      (value "1.0k")
      (footprint "eagle-import:R0402")
      (libsource (lib "eagle-import") (part "R-US_R0402"))
    )
    (comp (ref "R58")
      (value "1.0k")
      (footprint "eagle-import:R0402")
      (libsource (lib "eagle-import") (part "R-US_R0402"))
    )
    (comp (ref "R59")
      (value "1.0k")
      (footprint "eagle-import:R0402")
      (libsource (lib "eagle-import") (part "R-US_R0402"))
    )
    (comp (ref "C1")
      (value "22u")
      (footprint "eagle-import:C1206")
      (libsource (lib "eagle-import") (part "C-USC1206"))
    )
    (comp (ref "C2")
      (value "22u")
      (footprint "eagle-import:C1206")
      (libsource (lib "eagle-import") (part "C-USC1206"))
    )
    (comp (ref "C10")
      (value "22u")
      (footprint "eagle-import:C1206")
      (libsource (lib "eagle-import") (part "C-USC1206"))
    )
    (comp (ref "C15")
      (value "100n")
      (footprint "eagle-import:C0402")
      (libsource (lib "eagle-import") (part "C-USC0402"))
    )
    (comp (ref "C17")
      (value "22u")
      (footprint "eagle-import:C1206")
      (libsource (lib "eagle-import") (part "C-USC1206"))
    )
    (comp (ref "C19")
      (value "22u")
      (footprint "eagle-import:C1206")
      (libsource (lib "eagle-import") (part "C-USC1206"))
    )
    (comp (ref "C20")
      (value "22u")
      (footprint "eagle-import:C1206")
      (libsource (lib "eagle-import") (part "C-USC1206"))
    )
    (comp (ref "C21")
      (value "22u")
      (footprint "eagle-import:C1206")
      (libsource (lib "eagle-import") (part "C-USC1206"))
    )
    (comp (ref "C23")
      (value "22u")
      (footprint "eagle-import:C1206")
      (libsource (lib "eagle-import") (part "C-USC1206"))
    )
    (comp (ref "C25")
      (value "22u")
      (footprint "eagle-import:C1206")
      (libsource (lib "eagle-import") (part "C-USC1206"))
    )
    (comp (ref "C41")
      (value "1u")
      (footprint "eagle-import:C0402")
      (libsource (lib "eagle-import") (part "C-USC0402"))
    )
    (comp (ref "D1")
      (value "1N5819HW")
      (footprint "eagle-import:SOD123")
      (libsource (lib "eagle-import") (part "DIODE-SOD123"))
    )
    (comp (ref "D2")
      (value "1N5819HW")
      (footprint "eagle-import:SOD123")
      (libsource (lib "eagle-import") (part "DIODE-SOD123"))
    )
    (comp (ref "H3")
      (value "MOUNT-HOLE3.0TINY")
      (footprint "eagle-import:3,0TINY")
      (libsource (lib "eagle-import") (part "MOUNT-HOLE3.0TINY"))
    )
    (comp (ref "IC2")
      (value "ROF-78E3.3-0.5SMD")
      (footprint "eagle-import:ROF78EXX-0.5SMD")
      (libsource (lib "eagle-import") (part "ROF-78EXX-0.55SMD"))
    )
    (comp (ref "IC7")
      (value "LD2981ABU33")
      (footprint "eagle-import:SOT89")
      (libsource (lib "eagle-import") (part "LD2981ABU"))
    )
    (comp (ref "IC11")
      (value "LM4040B25")
      (footprint "eagle-import:DBZ_R-PDSO-G3")
      (libsource (lib "eagle-import") (part "LM4041DBZB12"))
    )
    (comp (ref "JP5")
      (value "M05X2SMD")
      (footprint "eagle-import:2X5-SMD")
      (libsource (lib "eagle-import") (part "M05X2SMD"))
    )
    (comp (ref "L1")
      (value "WE-CBF_0603")
      (footprint "eagle-import:0603")
      (libsource (lib "eagle-import") (part "WE-CBF_0603"))
    )
    (comp (ref "L3")
      (value "33u")
      (footprint "eagle-import:L2012C")
      (libsource (lib "eagle-import") (part "L-USL2012C"))
    )
    (comp (ref "L4")
      (value "WE-CBF_0603")
      (footprint "eagle-import:0603")
      (libsource (lib "eagle-import") (part "WE-CBF_0603"))
    )
    (comp (ref "L5")
      (value "WE-CBF_0603")
      (footprint "eagle-import:0603")
      (libsource (lib "eagle-import") (part "WE-CBF_0603"))
    )
    (comp (ref "R33")
      (value "10k")
      (footprint "eagle-import:R0402")
      (libsource (lib "eagle-import") (part "R-US_R0402"))
    )
    (comp (ref "D3")
      (value "1N4148")
      (footprint "eagle-import:SOD523")
      (libsource (lib "eagle-import") (part "DIODE-SOD523"))
    )
    (comp (ref "D4")
      (value "1N4148")
      (footprint "eagle-import:SOD523")
      (libsource (lib "eagle-import") (part "DIODE-SOD523"))
    )
    (comp (ref "D5")
      (value "1N4148")
      (footprint "eagle-import:SOD523")
      (libsource (lib "eagle-import") (part "DIODE-SOD523"))
    )
    (comp (ref "D6")
      (value "1N4148")
      (footprint "eagle-import:SOD523")
      (libsource (lib "eagle-import") (part "DIODE-SOD523"))
    )
    (comp (ref "D7")
      (value "1N4148")
      (footprint "eagle-import:SOD523")
      (libsource (lib "eagle-import") (part "DIODE-SOD523"))
    )
    (comp (ref "D8")
      (value "1N4148")
      (footprint "eagle-import:SOD523")
      (libsource (lib "eagle-import") (part "DIODE-SOD523"))
    )
    (comp (ref "D9")
      (value "BAT54S")
      (footprint "eagle-import:SOT23")
      (libsource (lib "eagle-import") (part "DIODE_2CACA-SOT23"))
    )
    (comp (ref "J7")
      (value "PJ301_THONKICONN6")
      (footprint "eagle-import:WQP_PJ_301M6")
      (libsource (lib "eagle-import") (part "PJ301_THONKICONN6"))
    )
    (comp (ref "J8")
      (value "PJ301_THONKICONN6")
      (footprint "eagle-import:WQP_PJ_301M6")
      (libsource (lib "eagle-import") (part "PJ301_THONKICONN6"))
    )
    (comp (ref "J9")
      (value "PJ301_THONKICONN6")
      (footprint "eagle-import:WQP_PJ_301M6")
      (libsource (lib "eagle-import") (part "PJ301_THONKICONN6"))
    )
    (comp (ref "J10")
      (value "PJ301_THONKICONN6")
      (footprint "eagle-import:WQP_PJ_301M6")
      (libsource (lib "eagle-import") (part "PJ301_THONKICONN6"))
    )
    (comp (ref "J11")
      (value "PJ301_THONKICONN6")
      (footprint "eagle-import:WQP_PJ_301M6")
      (libsource (lib "eagle-import") (part "PJ301_THONKICONN6"))
    )
    (comp (ref "J12")
      (value "PJ301_THONKICONN6")
      (footprint "eagle-import:WQP_PJ_301M6")
      (libsource (lib "eagle-import") (part "PJ301_THONKICONN6"))
    )
    (comp (ref "Q2")
      (value "MMBT3904")
      (footprint "eagle-import:SOT23-BEC")
      (libsource (lib "eagle-import") (part "-NPN-SOT23-BECMMBT3904LT1"))
    )
    (comp (ref "Q3")
      (value "MMBT3904")
      (footprint "eagle-import:SOT23-BEC")
      (libsource (lib "eagle-import") (part "-NPN-SOT23-BECMMBT3904LT1"))
    )
    (comp (ref "Q4")
      (value "MMBT3904")
      (footprint "eagle-import:SOT23-BEC")
      (libsource (lib "eagle-import") (part "-NPN-SOT23-BECMMBT3904LT1"))
    )
    (comp (ref "Q5")
      (value "MMBT3904")
      (footprint "eagle-import:SOT23-BEC")
      (libsource (lib "eagle-import") (part "-NPN-SOT23-BECMMBT3904LT1"))
    )
    (comp (ref "Q6")
      (value "MMBT3904")
      (footprint "eagle-import:SOT23-BEC")
      (libsource (lib "eagle-import") (part "-NPN-SOT23-BECMMBT3904LT1"))
    )
    (comp (ref "Q7")
      (value "MMBT3904")
      (footprint "eagle-import:SOT23-BEC")
      (libsource (lib "eagle-import") (part "-NPN-SOT23-BECMMBT3904LT1"))
    )
    (comp (ref "R60")
      (value "10k")
      (footprint "eagle-import:R0402")
      (libsource (lib "eagle-import") (part "R-US_R0402"))
    )
    (comp (ref "R61")
      (value "10k")
      (footprint "eagle-import:R0402")
      (libsource (lib "eagle-import") (part "R-US_R0402"))
    )
    (comp (ref "R62")
      (value "10k")
      (footprint "eagle-import:R0402")
      (libsource (lib "eagle-import") (part "R-US_R0402"))
    )
    (comp (ref "R63")
      (value "10k")
      (footprint "eagle-import:R0402")
      (libsource (lib "eagle-import") (part "R-US_R0402"))
    )
    (comp (ref "R64")
      (value "10k")
      (footprint "eagle-import:R0402")
      (libsource (lib "eagle-import") (part "R-US_R0402"))
    )
    (comp (ref "R65")
      (value "10k")
      (footprint "eagle-import:R0402")
      (libsource (lib "eagle-import") (part "R-US_R0402"))
    )
    (comp (ref "R66")
      (value "100k")
      (footprint "eagle-import:R0402")
      (libsource (lib "eagle-import") (part "R-US_R0402"))
    )
    (comp (ref "R67")
      (value "100k")
      (footprint "eagle-import:R0402")
      (libsource (lib "eagle-import") (part "R-US_R0402"))
    )
    (comp (ref "R68")
      (value "100k")
      (footprint "eagle-import:R0402")
      (libsource (lib "eagle-import") (part "R-US_R0402"))
    )
    (comp (ref "R69")
      (value "100k")
      (footprint "eagle-import:R0402")
      (libsource (lib "eagle-import") (part "R-US_R0402"))
    )
    (comp (ref "R70")
      (value "100k")
      (footprint "eagle-import:R0402")
      (libsource (lib "eagle-import") (part "R-US_R0402"))
    )
    (comp (ref "R71")
      (value "100k")
      (footprint "eagle-import:R0402")
      (libsource (lib "eagle-import") (part "R-US_R0402"))
    )
    (comp (ref "R72")
      (value "100k")
      (footprint "eagle-import:R0402")
      (libsource (lib "eagle-import") (part "R-US_R0402"))
    )
    (comp (ref "R73")
      (value "100k")
      (footprint "eagle-import:R0402")
      (libsource (lib "eagle-import") (part "R-US_R0402"))
    )
    (comp (ref "R74")
      (value "100k")
      (footprint "eagle-import:R0402")
      (libsource (lib "eagle-import") (part "R-US_R0402"))
    )
    (comp (ref "R75")
      (value "100k")
      (footprint "eagle-import:R0402")
      (libsource (lib "eagle-import") (part "R-US_R0402"))
    )
    (comp (ref "R76")
      (value "100k")
      (footprint "eagle-import:R0402")
      (libsource (lib "eagle-import") (part "R-US_R0402"))
    )
    (comp (ref "R77")
      (value "100k")
      (footprint "eagle-import:R0402")
      (libsource (lib "eagle-import") (part "R-US_R0402"))
    )
  )
  (nets
    (net (code "1") (name "+3V3") (class "Default")
      (node (ref "C10") (pin "1") (pinfunction "1_1") (pintype "passive"))
      (node (ref "C11") (pin "1") (pinfunction "1_1") (pintype "passive"))
      (node (ref "C14") (pin "1") (pinfunction "1_1") (pintype "passive"))
      (node (ref "C15") (pin "1") (pinfunction "1_1") (pintype "passive"))
      (node (ref "C9") (pin "1") (pinfunction "1_1") (pintype "passive"))
      (node (ref "D9") (pin "2") (pinfunction "C_2") (pintype "passive"))
      (node (ref "IC2") (pin "3") (pinfunction "VO_3") (pintype "passive"))
      (node (ref "IC5") (pin "1") (pinfunction "VBAT_1") (pintype "power_in"))
      (node (ref "IC5") (pin "19") (pinfunction "VDD_2_19") (pintype "power_in"))
      (node (ref "IC5") (pin "64") (pinfunction "VDD_1_64") (pintype "power_in"))
      (node (ref "L2") (pin "2") (pinfunction "2_2") (pintype "passive"))
      (node (ref "LED10") (pin "A") (pinfunction "A_A") (pintype "bidirectional"))
      (node (ref "LED11") (pin "A") (pinfunction "A_A") (pintype "bidirectional"))
      (node (ref "LED12") (pin "A") (pinfunction "A_A") (pintype "bidirectional"))
      (node (ref "LED7") (pin "A") (pinfunction "A_A") (pintype "bidirectional"))
      (node (ref "LED8") (pin "A") (pinfunction "A_A") (pintype "bidirectional"))
      (node (ref "LED9") (pin "A") (pinfunction "A_A") (pintype "bidirectional"))
      (node (ref "R12") (pin "2") (pinfunction "2_2") (pintype "passive"))
    )
    (net (code "2") (name "+3V3_A") (class "Default")
      (node (ref "C12") (pin "1") (pinfunction "1_1") (pintype "passive"))
      (node (ref "C13") (pin "1") (pinfunction "1_1") (pintype "passive"))
      (node (ref "C16") (pin "1") (pinfunction "1_1") (pintype "passive"))
      (node (ref "C18") (pin "1") (pinfunction "1_1") (pintype "passive"))
      (node (ref "C20") (pin "1") (pinfunction "1_1") (pintype "passive"))
      (node (ref "C22") (pin "1") (pinfunction "1_1") (pintype "passive"))
      (node (ref "C24") (pin "1") (pinfunction "1_1") (pintype "passive"))
      (node (ref "C26") (pin "1") (pinfunction "1_1") (pintype "passive"))
      (node (ref "C30") (pin "1") (pinfunction "1_1") (pintype "passive"))
      (node (ref "C33") (pin "1") (pinfunction "1_1") (pintype "passive"))
      (node (ref "C34") (pin "1") (pinfunction "1_1") (pintype "passive"))
      (node (ref "C5") (pin "1") (pinfunction "1_1") (pintype "passive"))
      (node (ref "C7") (pin "1") (pinfunction "1_1") (pintype "passive"))
      (node (ref "IC10") (pin "8") (pinfunction "V+_8") (pintype "power_in"))
      (node (ref "IC3") (pin "16") (pinfunction "VCC_16") (pintype "power_in"))
      (node (ref "IC4") (pin "2") (pinfunction "AVDD_2") (pintype "power_in"))
      (node (ref "IC5") (pin "13") (pinfunction "VDDA_13") (pintype "power_in"))
      (node (ref "IC5") (pin "17") (pinfunction "VREF+_17") (pintype "power_in"))
      (node (ref "IC5") (pin "32") (pinfunction "VDDSD_32") (pintype "power_in"))
      (node (ref "IC5") (pin "33") (pinfunction "VREFSD+_33") (pintype "power_in"))
      (node (ref "IC6") (pin "16") (pinfunction "VCC_16") (pintype "power_in"))
      (node (ref "IC7") (pin "1") (pinfunction "VO_1") (pintype "passive"))
      (node (ref "IC8") (pin "8") (pinfunction "V+_8") (pintype "power_in"))
      (node (ref "IC9") (pin "8") (pinfunction "V+_8") (pintype "power_in"))
      (node (ref "R78") (pin "3") (pinfunction "E_3") (pintype "passive"))
      (node (ref "R79") (pin "3") (pinfunction "E_3") (pintype "passive"))
      (node (ref "R80") (pin "3") (pinfunction "E_3") (pintype "passive"))
      (node (ref "R81") (pin "3") (pinfunction "E_3") (pintype "passive"))
      (node (ref "R82") (pin "3") (pinfunction "E_3") (pintype "passive"))
      (node (ref "R83") (pin "3") (pinfunction "E_3") (pintype "passive"))
      (node (ref "R84") (pin "P$1") (pinfunction "E_P$1") (pintype "passive"))
      (node (ref "R85") (pin "P$1") (pinfunction "E_P$1") (pintype "passive"))
      (node (ref "R86") (pin "P$1") (pinfunction "E_P$1") (pintype "passive"))
      (node (ref "R87") (pin "P$1") (pinfunction "E_P$1") (pintype "passive"))
      (node (ref "R88") (pin "P$1") (pinfunction "E_P$1") (pintype "passive"))
      (node (ref "R89") (pin "P$1") (pinfunction "E_P$1") (pintype "passive"))
    )
    (net (code "3") (name "ADC_CV_1") (class "Default")
      (node (ref "C35") (pin "2") (pinfunction "2_2") (pintype "passive"))
      (node (ref "IC10") (pin "7") (pinfunction "OUT_7") (pintype "output"))
      (node (ref "IC5") (pin "34") (pinfunction "PB14/SPI2_MISO/I2S2_MCK/USART3_RTS/SDADC3_AIN8P_34") (pintype "bidirectional"))
      (node (ref "R16") (pin "1") (pinfunction "1_1") (pintype "passive"))
    )
    (net (code "4") (name "ADC_CV_2") (class "Default")
      (node (ref "C32") (pin "2") (pinfunction "2_2") (pintype "passive"))
      (node (ref "IC10") (pin "1") (pinfunction "OUT_1") (pintype "output"))
      (node (ref "IC5") (pin "35") (pinfunction "PB15/SPI2_MOSI/I2S2_SD/SDADC3_AIN7P/SDADC3_AIN8M_35") (pintype "bidirectional"))
      (node (ref "R14") (pin "1") (pinfunction "1_1") (pintype "passive"))
    )
    (net (code "5") (name "ADC_CV_3") (class "Default")
      (node (ref "C31") (pin "2") (pinfunction "2_2") (pintype "passive"))
      (node (ref "IC5") (pin "29") (pinfunction "PE8/SDADC1_AIN8P/SDADC2_AIN8P_29") (pintype "bidirectional"))
      (node (ref "IC9") (pin "7") (pinfunction "OUT_7") (pintype "output"))
      (node (ref "R13") (pin "1") (pinfunction "1_1") (pintype "passive"))
    )
    (net (code "6") (name "ADC_CV_4") (class "Default")
      (node (ref "C29") (pin "2") (pinfunction "2_2") (pintype "passive"))
      (node (ref "IC5") (pin "30") (pinfunction "PE9/SDADC1_AIN7P/SDADC1_AIN8M/SDADC2_AIN7P/SDADC2_AIN8M_30") (pintype "bidirectional"))
      (node (ref "IC9") (pin "1") (pinfunction "OUT_1") (pintype "output"))
      (node (ref "R15") (pin "1") (pinfunction "1_1") (pintype "passive"))
    )
    (net (code "7") (name "ADC_CV_5") (class "Default")
      (node (ref "C27") (pin "2") (pinfunction "2_2") (pintype "passive"))
      (node (ref "IC5") (pin "27") (pinfunction "PB1/TIM3_CH4/ADC_IN9/SDADC1_AIN5P/SDADC1_AIN6M_27") (pintype "bidirectional"))
      (node (ref "IC8") (pin "7") (pinfunction "OUT_7") (pintype "output"))
      (node (ref "R19") (pin "1") (pinfunction "1_1") (pintype "passive"))
    )
    (net (code "8") (name "ADC_CV_6") (class "Default")
      (node (ref "C28") (pin "2") (pinfunction "2_2") (pintype "passive"))
      (node (ref "IC5") (pin "26") (pinfunction "PB0/SPI1_MOSI/I2S1_SD/TIM3_CH3/ADC_IN8/SDADC1_AIN6P_26") (pintype "bidirectional"))
      (node (ref "IC8") (pin "1") (pinfunction "OUT_1") (pintype "output"))
      (node (ref "R20") (pin "1") (pinfunction "1_1") (pintype "passive"))
    )
    (net (code "9") (name "ADC_SHAPE") (class "Default")
      (node (ref "IC3") (pin "3") (pinfunction "X_3") (pintype "bidirectional"))
      (node (ref "IC5") (pin "22") (pinfunction "PA6/SPI1_MISO/I2S1_MCK/TIM3_CH1/ADC_IN6/DAC2_OUT1_22") (pintype "bidirectional"))
    )
    (net (code "10") (name "ADC_TIME_LEVEL") (class "Default")
      (node (ref "IC5") (pin "23") (pinfunction "PA7/SPI1_MOSI/I2S1_SD/TIM3_CH2/ADC_IN7_23") (pintype "bidirectional"))
      (node (ref "IC6") (pin "3") (pinfunction "X_3") (pintype "bidirectional"))
    )
    (net (code "11") (name "AREF_-2.5") (class "Default")
      (node (ref "C41") (pin "1") (pinfunction "1_1") (pintype "passive"))
      (node (ref "IC11") (pin "2") (pinfunction "A_2") (pintype "passive"))
      (node (ref "R21") (pin "2") (pinfunction "2_2") (pintype "passive"))
      (node (ref "R22") (pin "2") (pinfunction "2_2") (pintype "passive"))
      (node (ref "R23") (pin "2") (pinfunction "2_2") (pintype "passive"))
      (node (ref "R24") (pin "2") (pinfunction "2_2") (pintype "passive"))
      (node (ref "R26") (pin "2") (pinfunction "2_2") (pintype "passive"))
      (node (ref "R29") (pin "2") (pinfunction "2_2") (pintype "passive"))
      (node (ref "R33") (pin "2") (pinfunction "2_2") (pintype "passive"))
    )
    (net (code "12") (name "AREF_2.5") (class "Default")
      (node (ref "IC4") (pin "7") (pinfunction "VREF_7") (pintype "input"))
      (node (ref "R40") (pin "2") (pinfunction "2_2") (pintype "passive"))
    )
    (net (code "13") (name "DAC_1") (class "Default")
      (node (ref "IC4") (pin "10") (pinfunction "VOUTD_10") (pintype "output"))
      (node (ref "R52") (pin "2") (pinfunction "2_2") (pintype "passive"))
    )
    (net (code "14") (name "DAC_2") (class "Default")
      (node (ref "IC4") (pin "11") (pinfunction "VOUTB_11") (pintype "output"))
      (node (ref "R51") (pin "2") (pinfunction "2_2") (pintype "passive"))
    )
    (net (code "15") (name "DAC_3") (class "Default")
      (node (ref "IC4") (pin "6") (pinfunction "VOUTG_6") (pintype "output"))
      (node (ref "R53") (pin "2") (pinfunction "2_2") (pintype "passive"))
    )
    (net (code "16") (name "DAC_4") (class "Default")
      (node (ref "IC4") (pin "4") (pinfunction "VOUTC_4") (pintype "output"))
      (node (ref "R49") (pin "2") (pinfunction "2_2") (pintype "passive"))
    )
    (net (code "17") (name "DAC_5") (class "Default")
      (node (ref "IC4") (pin "3") (pinfunction "VOUTA_3") (pintype "output"))
      (node (ref "R50") (pin "2") (pinfunction "2_2") (pintype "passive"))
    )
    (net (code "18") (name "DAC_6") (class "Default")
      (node (ref "IC4") (pin "5") (pinfunction "VOUTE_5") (pintype "output"))
      (node (ref "R47") (pin "2") (pinfunction "2_2") (pintype "passive"))
    )
    (net (code "19") (name "DAC_MOSI") (class "Default")
      (node (ref "IC4") (pin "13") (pinfunction "DIN_13") (pintype "input"))
      (node (ref "IC5") (pin "53") (pinfunction "PC12/SPI3_MOSI/I2S3_SD/USART3_CK_53") (pintype "bidirectional"))
    )
    (net (code "20") (name "DAC_SCK") (class "Default")
      (node (ref "IC4") (pin "14") (pinfunction "SCLK_14") (pintype "input"))
      (node (ref "IC5") (pin "51") (pinfunction "PC10/SPI3_SCK/I2S3_CK/USART3_TX_51") (pintype "bidirectional"))
    )
    (net (code "21") (name "DAC_SS") (class "Default")
      (node (ref "IC4") (pin "1") (pinfunction "~{SYNC}_1") (pintype "input"))
      (node (ref "IC5") (pin "50") (pinfunction "PA15/SPI1_NSS/I2S1_WS/SPI3_NSS/I2S3_WS/I2C1_SCL/TIM2_CH1_ETR/JTDI_50") (pintype "bidirectional"))
    )
    (net (code "22") (name "GATE_1") (class "Default")
      (node (ref "IC5") (pin "44") (pinfunction "PA11/SPI2_NSS/I2S2_WS/SPI1_NSS/I2S1_WS/USART1_CTS/CAN_RX/TIM4_CH1/TIM5_CH2_44") (pintype "bidirectional"))
      (node (ref "Q7") (pin "C") (pinfunction "C_C") (pintype "passive"))
    )
    (net (code "23") (name "GATE_2") (class "Default")
      (node (ref "IC5") (pin "43") (pinfunction "PA10/SPI2_MOSI/I2S2_SD/I2C2_SDA/USART1_RX/TIM2_CH4_43") (pintype "bidirectional"))
      (node (ref "Q3") (pin "C") (pinfunction "C_C") (pintype "passive"))
    )
    (net (code "24") (name "GATE_3") (class "Default")
      (node (ref "IC5") (pin "42") (pinfunction "PA9/SPI_MISO/I2S2_MCK/I2C2_SCL/USART1_TX/TIM2_CH3_42") (pintype "bidirectional"))
      (node (ref "Q6") (pin "C") (pinfunction "C_C") (pintype "passive"))
    )
    (net (code "25") (name "GATE_4") (class "Default")
      (node (ref "IC5") (pin "41") (pinfunction "PA8/SPI2_SCK/I2S2_CK/I2C2_SMBA/USART1_CK/TIM5_CH1_41") (pintype "bidirectional"))
      (node (ref "Q4") (pin "C") (pinfunction "C_C") (pintype "passive"))
    )
    (net (code "26") (name "GATE_5") (class "Default")
      (node (ref "IC5") (pin "39") (pinfunction "PC8/SPI1_MISO/I2S1_MCK/TIM3_CH3_39") (pintype "bidirectional"))
      (node (ref "Q5") (pin "C") (pinfunction "C_C") (pintype "passive"))
    )
    (net (code "27") (name "GATE_6") (class "Default")
      (node (ref "IC5") (pin "38") (pinfunction "PC7/SPI1_SCK/I2S1_CK/TIM3_CH2_38") (pintype "bidirectional"))
      (node (ref "Q2") (pin "C") (pinfunction "C_C") (pintype "passive"))
    )
    (net (code "28") (name "GND") (class "Default")
      (node (ref "C1") (pin "1") (pinfunction "1_1") (pintype "passive"))
      (node (ref "C10") (pin "2") (pinfunction "2_2") (pintype "passive"))
      (node (ref "C11") (pin "2") (pinfunction "2_2") (pintype "passive"))
      (node (ref "C12") (pin "2") (pinfunction "2_2") (pintype "passive"))
      (node (ref "C13") (pin "2") (pinfunction "2_2") (pintype "passive"))
      (node (ref "C14") (pin "2") (pinfunction "2_2") (pintype "passive"))
      (node (ref "C15") (pin "2") (pinfunction "2_2") (pintype "passive"))
      (node (ref "C16") (pin "2") (pinfunction "2_2") (pintype "passive"))
      (node (ref "C17") (pin "2") (pinfunction "2_2") (pintype "passive"))
      (node (ref "C18") (pin "2") (pinfunction "2_2") (pintype "passive"))
      (node (ref "C19") (pin "2") (pinfunction "2_2") (pintype "passive"))
      (node (ref "C2") (pin "1") (pinfunction "1_1") (pintype "passive"))
      (node (ref "C20") (pin "2") (pinfunction "2_2") (pintype "passive"))
      (node (ref "C21") (pin "2") (pinfunction "2_2") (pintype "passive"))
      (node (ref "C22") (pin "2") (pinfunction "2_2") (pintype "passive"))
      (node (ref "C23") (pin "2") (pinfunction "2_2") (pintype "passive"))
      (node (ref "C24") (pin "2") (pinfunction "2_2") (pintype "passive"))
      (node (ref "C25") (pin "2") (pinfunction "2_2") (pintype "passive"))
      (node (ref "C26") (pin "2") (pinfunction "2_2") (pintype "passive"))
      (node (ref "C3") (pin "1") (pinfunction "1_1") (pintype "passive"))
      (node (ref "C30") (pin "2") (pinfunction "2_2") (pintype "passive"))
      (node (ref "C33") (pin "2") (pinfunction "2_2") (pintype "passive"))
      (node (ref "C34") (pin "2") (pinfunction "2_2") (pintype "passive"))
      (node (ref "C36") (pin "2") (pinfunction "2_2") (pintype "passive"))
      (node (ref "C37") (pin "2") (pinfunction "2_2") (pintype "passive"))
      (node (ref "C38") (pin "2") (pinfunction "2_2") (pintype "passive"))
      (node (ref "C39") (pin "2") (pinfunction "2_2") (pintype "passive"))
      (node (ref "C4") (pin "1") (pinfunction "1_1") (pintype "passive"))
      (node (ref "C40") (pin "2") (pinfunction "2_2") (pintype "passive"))
      (node (ref "C41") (pin "2") (pinfunction "2_2") (pintype "passive"))
      (node (ref "C42") (pin "2") (pinfunction "2_2") (pintype "passive"))
      (node (ref "C43") (pin "2") (pinfunction "2_2") (pintype "passive"))
      (node (ref "C5") (pin "2") (pinfunction "2_2") (pintype "passive"))
      (node (ref "C50") (pin "2") (pinfunction "2_2") (pintype "passive"))
      (node (ref "C51") (pin "1") (pinfunction "1_1") (pintype "passive"))
      (node (ref "C52") (pin "2") (pinfunction "2_2") (pintype "passive"))
      (node (ref "C53") (pin "1") (pinfunction "1_1") (pintype "passive"))
      (node (ref "C54") (pin "2") (pinfunction "2_2") (pintype "passive"))
      (node (ref "C55") (pin "1") (pinfunction "1_1") (pintype "passive"))
      (node (ref "C6") (pin "2") (pinfunction "2_2") (pintype "passive"))
      (node (ref "C7") (pin "2") (pinfunction "2_2") (pintype "passive"))
      (node (ref "C8") (pin "2") (pinfunction "2_2") (pintype "passive"))
      (node (ref "C9") (pin "2") (pinfunction "2_2") (pintype "passive"))
      (node (ref "D3") (pin "A") (pinfunction "A_A") (pintype "passive"))
      (node (ref "D4") (pin "A") (pinfunction "A_A") (pintype "passive"))
      (node (ref "D5") (pin "A") (pinfunction "A_A") (pintype "passive"))
      (node (ref "D6") (pin "A") (pinfunction "A_A") (pintype "passive"))
      (node (ref "D7") (pin "A") (pinfunction "A_A") (pintype "passive"))
      (node (ref "D8") (pin "A") (pinfunction "A_A") (pintype "passive"))
      (node (ref "D9") (pin "1") (pinfunction "A_1") (pintype "passive"))
      (node (ref "IC1") (pin "1") (pinfunction "GND_1") (pintype "bidirectional"))
      (node (ref "IC1") (pin "21") (pinfunction "BLANK_21") (pintype "bidirectional"))
      (node (ref "IC10") (pin "3") (pinfunction "+IN_3") (pintype "input"))
      (node (ref "IC10") (pin "4") (pinfunction "V-_4") (pintype "power_in"))
      (node (ref "IC10") (pin "5") (pinfunction "+IN_5") (pintype "input"))
      (node (ref "IC11") (pin "1") (pinfunction "C_1") (pintype "passive"))
      (node (ref "IC2") (pin "2") (pinfunction "GND_2") (pintype "passive"))
      (node (ref "IC3") (pin "6") (pinfunction "INH_6") (pintype "input"))
      (node (ref "IC3") (pin "7") (pinfunction "VEE_7") (pintype "power_in"))
      (node (ref "IC3") (pin "8") (pinfunction "GND_8") (pintype "power_in"))
      (node (ref "IC4") (pin "12") (pinfunction "GND_12") (pintype "passive"))
      (node (ref "IC5") (pin "12") (pinfunction "VSSA_12") (pintype "power_in"))
      (node (ref "IC5") (pin "31") (pinfunction "VSSSD/VREFSD-_31") (pintype "power_in"))
      (node (ref "IC5") (pin "60") (pinfunction "BOOT0_60") (pintype "bidirectional"))
      (node (ref "IC5") (pin "63") (pinfunction "VSS_1_63") (pintype "power_in"))
      (node (ref "IC6") (pin "6") (pinfunction "INH_6") (pintype "input"))
      (node (ref "IC6") (pin "7") (pinfunction "VEE_7") (pintype "power_in"))
      (node (ref "IC6") (pin "8") (pinfunction "GND_8") (pintype "power_in"))
      (node (ref "IC7") (pin "2") (pinfunction "GND_2") (pintype "passive"))
      (node (ref "IC8") (pin "3") (pinfunction "+IN_3") (pintype "input"))
      (node (ref "IC8") (pin "4") (pinfunction "V-_4") (pintype "power_in"))
      (node (ref "IC8") (pin "5") (pinfunction "+IN_5") (pintype "input"))
      (node (ref "IC9") (pin "3") (pinfunction "+IN_3") (pintype "input"))
      (node (ref "IC9") (pin "4") (pinfunction "V-_4") (pintype "power_in"))
      (node (ref "IC9") (pin "5") (pinfunction "+IN_5") (pintype "input"))
      (node (ref "J1") (pin "P1") (pinfunction "1_P1") (pintype "passive"))
      (node (ref "J10") (pin "P1") (pinfunction "1_P1") (pintype "passive"))
      (node (ref "J11") (pin "P1") (pinfunction "1_P1") (pintype "passive"))
      (node (ref "J12") (pin "P1") (pinfunction "1_P1") (pintype "passive"))
      (node (ref "J13") (pin "P1") (pinfunction "1_P1") (pintype "passive"))
      (node (ref "J13") (pin "P2") (pinfunction "2_P2") (pintype "passive"))
      (node (ref "J14") (pin "P1") (pinfunction "1_P1") (pintype "passive"))
      (node (ref "J14") (pin "P2") (pinfunction "2_P2") (pintype "passive"))
      (node (ref "J15") (pin "P1") (pinfunction "1_P1") (pintype "passive"))
      (node (ref "J15") (pin "P2") (pinfunction "2_P2") (pintype "passive"))
      (node (ref "J16") (pin "P1") (pinfunction "1_P1") (pintype "passive"))
      (node (ref "J16") (pin "P2") (pinfunction "2_P2") (pintype "passive"))
      (node (ref "J17") (pin "P1") (pinfunction "1_P1") (pintype "passive"))
      (node (ref "J17") (pin "P2") (pinfunction "2_P2") (pintype "passive"))
      (node (ref "J18") (pin "P1") (pinfunction "1_P1") (pintype "passive"))
      (node (ref "J18") (pin "P2") (pinfunction "2_P2") (pintype "passive"))
      (node (ref "J2") (pin "P1") (pinfunction "1_P1") (pintype "passive"))
      (node (ref "J3") (pin "P1") (pinfunction "1_P1") (pintype "passive"))
      (node (ref "J4") (pin "P1") (pinfunction "1_P1") (pintype "passive"))
      (node (ref "J5") (pin "P1") (pinfunction "1_P1") (pintype "passive"))
      (node (ref "J6") (pin "P1") (pinfunction "1_P1") (pintype "passive"))
      (node (ref "J7") (pin "P1") (pinfunction "1_P1") (pintype "passive"))
      (node (ref "J8") (pin "P1") (pinfunction "1_P1") (pintype "passive"))
      (node (ref "J9") (pin "P1") (pinfunction "1_P1") (pintype "passive"))
      (node (ref "JP3") (pin "1") (pinfunction "1_1") (pintype "passive"))
      (node (ref "JP4") (pin "1") (pinfunction "1_1") (pintype "passive"))
      (node (ref "JP5") (pin "3") (pinfunction "3_3") (pintype "passive"))
      (node (ref "JP5") (pin "4") (pinfunction "4_4") (pintype "passive"))
      (node (ref "JP5") (pin "5") (pinfunction "5_5") (pintype "passive"))
      (node (ref "JP5") (pin "6") (pinfunction "6_6") (pintype "passive"))
      (node (ref "JP5") (pin "7") (pinfunction "7_7") (pintype "passive"))
      (node (ref "JP5") (pin "8") (pinfunction "8_8") (pintype "passive"))
      (node (ref "JP6") (pin "1") (pinfunction "1_1") (pintype "passive"))
      (node (ref "Q1") (pin "2") (pinfunction "LID1_2") (pintype "power_in"))
      (node (ref "Q1") (pin "4") (pinfunction "LID2_4") (pintype "power_in"))
      (node (ref "Q2") (pin "E") (pinfunction "E_E") (pintype "passive"))
      (node (ref "Q3") (pin "E") (pinfunction "E_E") (pintype "passive"))
      (node (ref "Q4") (pin "E") (pinfunction "E_E") (pintype "passive"))
      (node (ref "Q5") (pin "E") (pinfunction "E_E") (pintype "passive"))
      (node (ref "Q6") (pin "E") (pinfunction "E_E") (pintype "passive"))
      (node (ref "Q7") (pin "E") (pinfunction "E_E") (pintype "passive"))
      (node (ref "R48") (pin "1") (pinfunction "1_1") (pintype "passive"))
      (node (ref "R54") (pin "2") (pinfunction "2_2") (pintype "passive"))
      (node (ref "R55") (pin "2") (pinfunction "2_2") (pintype "passive"))
      (node (ref "R56") (pin "2") (pinfunction "2_2") (pintype "passive"))
      (node (ref "R57") (pin "2") (pinfunction "2_2") (pintype "passive"))
      (node (ref "R58") (pin "2") (pinfunction "2_2") (pintype "passive"))
      (node (ref "R59") (pin "2") (pinfunction "2_2") (pintype "passive"))
      (node (ref "R6") (pin "2") (pinfunction "2_2") (pintype "passive"))
      (node (ref "R69") (pin "1") (pinfunction "1_1") (pintype "passive"))
      (node (ref "R70") (pin "1") (pinfunction "1_1") (pintype "passive"))
      (node (ref "R71") (pin "1") (pinfunction "1_1") (pintype "passive"))
      (node (ref "R72") (pin "1") (pinfunction "1_1") (pintype "passive"))
      (node (ref "R73") (pin "1") (pinfunction "1_1") (pintype "passive"))
      (node (ref "R74") (pin "1") (pinfunction "1_1") (pintype "passive"))
      (node (ref "R78") (pin "1") (pinfunction "A_1") (pintype "passive"))
      (node (ref "R78") (pin "E") (pinfunction "C_E") (pintype "passive"))
      (node (ref "R79") (pin "1") (pinfunction "A_1") (pintype "passive"))
      (node (ref "R79") (pin "E") (pinfunction "C_E") (pintype "passive"))
      (node (ref "R80") (pin "1") (pinfunction "A_1") (pintype "passive"))
      (node (ref "R80") (pin "E") (pinfunction "C_E") (pintype "passive"))
      (node (ref "R81") (pin "1") (pinfunction "A_1") (pintype "passive"))
      (node (ref "R81") (pin "E") (pinfunction "C_E") (pintype "passive"))
      (node (ref "R82") (pin "1") (pinfunction "A_1") (pintype "passive"))
      (node (ref "R82") (pin "E") (pinfunction "C_E") (pintype "passive"))
      (node (ref "R83") (pin "1") (pinfunction "A_1") (pintype "passive"))
      (node (ref "R83") (pin "E") (pinfunction "C_E") (pintype "passive"))
      (node (ref "R84") (pin "P$3") (pinfunction "A_P$3") (pintype "passive"))
      (node (ref "R85") (pin "P$3") (pinfunction "A_P$3") (pintype "passive"))
      (node (ref "R86") (pin "P$3") (pinfunction "A_P$3") (pintype "passive"))
      (node (ref "R87") (pin "P$3") (pinfunction "A_P$3") (pintype "passive"))
      (node (ref "R88") (pin "P$3") (pinfunction "A_P$3") (pintype "passive"))
      (node (ref "R89") (pin "P$3") (pinfunction "A_P$3") (pintype "passive"))
      (node (ref "SW1") (pin "1") (pinfunction "1_1") (pintype "passive"))
      (node (ref "SW1") (pin "2") (pinfunction "2_2") (pintype "passive"))
      (node (ref "SW2") (pin "1") (pinfunction "1_1") (pintype "passive"))
      (node (ref "SW2") (pin "2") (pinfunction "2_2") (pintype "passive"))
      (node (ref "SW3") (pin "1") (pinfunction "1_1") (pintype "passive"))
      (node (ref "SW3") (pin "2") (pinfunction "2_2") (pintype "passive"))
      (node (ref "SW4") (pin "1") (pinfunction "1_1") (pintype "passive"))
      (node (ref "SW4") (pin "2") (pinfunction "2_2") (pintype "passive"))
      (node (ref "SW5") (pin "1") (pinfunction "1_1") (pintype "passive"))
      (node (ref "SW5") (pin "2") (pinfunction "2_2") (pintype "passive"))
      (node (ref "SW6") (pin "1") (pinfunction "1_1") (pintype "passive"))
      (node (ref "SW6") (pin "2") (pinfunction "2_2") (pintype "passive"))
    )
    (net (code "29") (name "LEDS_SCK") (class "Default")
      (node (ref "IC1") (pin "3") (pinfunction "SCLK_3") (pintype "bidirectional"))
      (node (ref "IC5") (pin "58") (pinfunction "PB6/I2C1_SCL/USART1_TX/TIM4_CH1_58") (pintype "bidirectional"))
    )
    (net (code "30") (name "LEDS_SIN") (class "Default")
      (node (ref "IC1") (pin "2") (pinfunction "SIN_2") (pintype "bidirectional"))
      (node (ref "IC5") (pin "57") (pinfunction "PB5/SPI1_MOSI/I2S1_SD/SPI3_MOSI/I2S3_SD/I2C1_SMBAI/USART2_CK/TIM3_CH2_57") (pintype "bidirectional"))
    )
    (net (code "31") (name "LEDS_SS") (class "Default")
      (node (ref "IC1") (pin "4") (pinfunction "LAT_4") (pintype "bidirectional"))
      (node (ref "IC5") (pin "59") (pinfunction "PB7/I2C1_SDA/USART1_RX/TIM4_CH2_59") (pintype "bidirectional"))
    )
    (net (code "32") (name "LEFT_RX") (class "Default")
      (node (ref "IC5") (pin "62") (pinfunction "PB9/SPI2_NSS/I2S2_WS/I2C1_SDA/USART3_RX/CAN_TX/TIM4_CH4_62") (pintype "bidirectional"))
      (node (ref "R7") (pin "1") (pinfunction "1_1") (pintype "passive"))
    )
    (net (code "33") (name "LEFT_TX") (class "Default")
      (node (ref "IC5") (pin "61") (pinfunction "PB8/SPI2_SCK/I2S2_CK/I2C1_SCL/USART3_TX/CAN_RX/TIM4_CH3_61") (pintype "bidirectional"))
      (node (ref "R5") (pin "1") (pinfunction "1_1") (pintype "passive"))
    )
    (net (code "34") (name "NORMALIZATION_PROBE") (class "Default")
      (node (ref "D9") (pin "3") (pinfunction "AC_3") (pintype "passive"))
      (node (ref "IC5") (pin "40") (pinfunction "PC9/SPI1_MOSI/I2S1_SD/TIM3_CH4_40") (pintype "bidirectional"))
      (node (ref "R60") (pin "1") (pinfunction "1_1") (pintype "passive"))
      (node (ref "R61") (pin "1") (pinfunction "1_1") (pintype "passive"))
      (node (ref "R62") (pin "1") (pinfunction "1_1") (pintype "passive"))
      (node (ref "R63") (pin "1") (pinfunction "1_1") (pintype "passive"))
      (node (ref "R64") (pin "1") (pinfunction "1_1") (pintype "passive"))
      (node (ref "R65") (pin "1") (pinfunction "1_1") (pintype "passive"))
    )
    (net (code "35") (name "Net-(C3-Pad2)") (class "Default")
      (node (ref "C3") (pin "2") (pinfunction "2_2") (pintype "passive"))
      (node (ref "Q1") (pin "1") (pinfunction "1_1") (pintype "passive"))
      (node (ref "R9") (pin "2") (pinfunction "2_2") (pintype "passive"))
    )
    (net (code "36") (name "Net-(C17-Pad1)") (class "Default")
      (node (ref "C17") (pin "1") (pinfunction "1_1") (pintype "passive"))
      (node (ref "D2") (pin "C") (pinfunction "C_C") (pintype "passive"))
      (node (ref "L3") (pin "1") (pinfunction "1_1") (pintype "passive"))
      (node (ref "L4") (pin "2") (pinfunction "2_2") (pintype "passive"))
      (node (ref "L5") (pin "2") (pinfunction "2_2") (pintype "passive"))
    )
    (net (code "37") (name "Net-(D1-PadA)") (class "Default")
      (node (ref "D1") (pin "A") (pinfunction "A_A") (pintype "passive"))
      (node (ref "L1") (pin "2") (pinfunction "2_2") (pintype "passive"))
    )
    (net (code "38") (name "Net-(D1-PadC)") (class "Default")
      (node (ref "D1") (pin "C") (pinfunction "C_C") (pintype "passive"))
      (node (ref "JP5") (pin "10") (pinfunction "10_10") (pintype "passive"))
      (node (ref "JP5") (pin "9") (pinfunction "9_9") (pintype "passive"))
    )
    (net (code "39") (name "Net-(D2-PadA)") (class "Default")
      (node (ref "D2") (pin "A") (pinfunction "A_A") (pintype "passive"))
      (node (ref "JP5") (pin "1") (pinfunction "1_1") (pintype "passive"))
      (node (ref "JP5") (pin "2") (pinfunction "2_2") (pintype "passive"))
    )
    (net (code "40") (name "Net-(D3-PadC)") (class "Default")
      (node (ref "D3") (pin "C") (pinfunction "C_C") (pintype "passive"))
      (node (ref "Q7") (pin "B") (pinfunction "B_B") (pintype "passive"))
      (node (ref "R66") (pin "2") (pinfunction "2_2") (pintype "passive"))
      (node (ref "R69") (pin "2") (pinfunction "2_2") (pintype "passive"))
    )
    (net (code "41") (name "Net-(D4-PadC)") (class "Default")
      (node (ref "D4") (pin "C") (pinfunction "C_C") (pintype "passive"))
      (node (ref "Q5") (pin "B") (pinfunction "B_B") (pintype "passive"))
      (node (ref "R67") (pin "2") (pinfunction "2_2") (pintype "passive"))
      (node (ref "R70") (pin "2") (pinfunction "2_2") (pintype "passive"))
    )
    (net (code "42") (name "Net-(D5-PadC)") (class "Default")
      (node (ref "D5") (pin "C") (pinfunction "C_C") (pintype "passive"))
      (node (ref "Q6") (pin "B") (pinfunction "B_B") (pintype "passive"))
      (node (ref "R68") (pin "2") (pinfunction "2_2") (pintype "passive"))
      (node (ref "R71") (pin "2") (pinfunction "2_2") (pintype "passive"))
    )
    (net (code "43") (name "Net-(D6-PadC)") (class "Default")
      (node (ref "D6") (pin "C") (pinfunction "C_C") (pintype "passive"))
      (node (ref "Q2") (pin "B") (pinfunction "B_B") (pintype "passive"))
      (node (ref "R74") (pin "2") (pinfunction "2_2") (pintype "passive"))
      (node (ref "R75") (pin "2") (pinfunction "2_2") (pintype "passive"))
    )
    (net (code "44") (name "Net-(D7-PadC)") (class "Default")
      (node (ref "D7") (pin "C") (pinfunction "C_C") (pintype "passive"))
      (node (ref "Q3") (pin "B") (pinfunction "B_B") (pintype "passive"))
      (node (ref "R73") (pin "2") (pinfunction "2_2") (pintype "passive"))
      (node (ref "R77") (pin "2") (pinfunction "2_2") (pintype "passive"))
    )
    (net (code "45") (name "Net-(D8-PadC)") (class "Default")
      (node (ref "D8") (pin "C") (pinfunction "C_C") (pintype "passive"))
      (node (ref "Q4") (pin "B") (pinfunction "B_B") (pintype "passive"))
      (node (ref "R72") (pin "2") (pinfunction "2_2") (pintype "passive"))
      (node (ref "R76") (pin "2") (pinfunction "2_2") (pintype "passive"))
    )
    (net (code "46") (name "Net-(IC1-IREF)") (class "Default")
      (node (ref "IC1") (pin "23") (pinfunction "IREF_23") (pintype "bidirectional"))
      (node (ref "R6") (pin "1") (pinfunction "1_1") (pintype "passive"))
    )
    (net (code "47") (name "Net-(IC1-OUT2)") (class "Default")
      (node (ref "IC1") (pin "7") (pinfunction "OUT2_7") (pintype "bidirectional"))
      (node (ref "LED9") (pin "RED_C") (pinfunction "RED_RED_C") (pintype "bidirectional"))
    )
    (net (code "48") (name "Net-(IC1-OUT3)") (class "Default")
      (node (ref "IC1") (pin "8") (pinfunction "OUT3_8") (pintype "bidirectional"))
      (node (ref "LED9") (pin "GREEN_C") (pinfunction "GRN_GREEN_C") (pintype "bidirectional"))
    )
    (net (code "49") (name "Net-(IC1-OUT4)") (class "Default")
      (node (ref "IC1") (pin "9") (pinfunction "OUT4_9") (pintype "bidirectional"))
      (node (ref "LED7") (pin "GREEN_C") (pinfunction "GRN_GREEN_C") (pintype "bidirectional"))
    )
    (net (code "50") (name "Net-(IC1-OUT5)") (class "Default")
      (node (ref "IC1") (pin "10") (pinfunction "OUT5_10") (pintype "bidirectional"))
      (node (ref "LED7") (pin "RED_C") (pinfunction "RED_RED_C") (pintype "bidirectional"))
    )
    (net (code "51") (name "Net-(IC1-OUT6)") (class "Default")
      (node (ref "IC1") (pin "11") (pinfunction "OUT6_11") (pintype "bidirectional"))
      (node (ref "LED8") (pin "GREEN_C") (pinfunction "GRN_GREEN_C") (pintype "bidirectional"))
    )
    (net (code "52") (name "Net-(IC1-OUT7)") (class "Default")
      (node (ref "IC1") (pin "12") (pinfunction "OUT7_12") (pintype "bidirectional"))
      (node (ref "LED8") (pin "RED_C") (pinfunction "RED_RED_C") (pintype "bidirectional"))
    )
    (net (code "53") (name "Net-(IC1-OUT8)") (class "Default")
      (node (ref "IC1") (pin "13") (pinfunction "OUT8_13") (pintype "bidirectional"))
      (node (ref "LED10") (pin "GREEN_C") (pinfunction "GRN_GREEN_C") (pintype "bidirectional"))
    )
    (net (code "54") (name "Net-(IC1-OUT9)") (class "Default")
      (node (ref "IC1") (pin "14") (pinfunction "OUT9_14") (pintype "bidirectional"))
      (node (ref "LED10") (pin "RED_C") (pinfunction "RED_RED_C") (pintype "bidirectional"))
    )
    (net (code "55") (name "Net-(IC1-OUT10)") (class "Default")
      (node (ref "IC1") (pin "15") (pinfunction "OUT10_15") (pintype "bidirectional"))
      (node (ref "LED11") (pin "RED_C") (pinfunction "RED_RED_C") (pintype "bidirectional"))
    )
    (net (code "56") (name "Net-(IC1-OUT11)") (class "Default")
      (node (ref "IC1") (pin "16") (pinfunction "OUT11_16") (pintype "bidirectional"))
      (node (ref "LED11") (pin "GREEN_C") (pinfunction "GRN_GREEN_C") (pintype "bidirectional"))
    )
    (net (code "57") (name "Net-(IC1-OUT12)") (class "Default")
      (node (ref "IC1") (pin "17") (pinfunction "OUT12_17") (pintype "bidirectional"))
      (node (ref "LED12") (pin "RED_C") (pinfunction "RED_RED_C") (pintype "bidirectional"))
    )
    (net (code "58") (name "Net-(IC1-OUT13)") (class "Default")
      (node (ref "IC1") (pin "18") (pinfunction "OUT13_18") (pintype "bidirectional"))
      (node (ref "LED12") (pin "GREEN_C") (pinfunction "GRN_GREEN_C") (pintype "bidirectional"))
    )
    (net (code "59") (name "Net-(IC1-VCC)") (class "Default")
      (node (ref "C6") (pin "1") (pinfunction "1_1") (pintype "passive"))
      (node (ref "C8") (pin "1") (pinfunction "1_1") (pintype "passive"))
      (node (ref "IC1") (pin "24") (pinfunction "VCC_24") (pintype "bidirectional"))
      (node (ref "L2") (pin "1") (pinfunction "1_1") (pintype "passive"))
    )
    (net (code "60") (name "Net-(IC2-VI)") (class "Default")
      (node (ref "C19") (pin "1") (pinfunction "1_1") (pintype "passive"))
      (node (ref "IC2") (pin "1") (pinfunction "VI_1") (pintype "input"))
      (node (ref "L3") (pin "2") (pinfunction "2_2") (pintype "passive"))
    )
    (net (code "61") (name "Net-(IC3A-X1)") (class "Default")
      (node (ref "IC3") (pin "14") (pinfunction "X1_14") (pintype "bidirectional"))
      (node (ref "R87") (pin "P$2") (pinfunction "S_P$2") (pintype "passive"))
    )
    (net (code "62") (name "Net-(IC3A-X2)") (class "Default")
      (node (ref "IC3") (pin "15") (pinfunction "X2_15") (pintype "bidirectional"))
      (node (ref "R88") (pin "P$2") (pinfunction "S_P$2") (pintype "passive"))
    )
    (net (code "63") (name "Net-(IC3A-X4)") (class "Default")
      (node (ref "IC3") (pin "1") (pinfunction "X4_1") (pintype "bidirectional"))
      (node (ref "R86") (pin "P$2") (pinfunction "S_P$2") (pintype "passive"))
    )
    (net (code "64") (name "Net-(IC3A-X5)") (class "Default")
      (node (ref "IC3") (pin "5") (pinfunction "X5_5") (pintype "bidirectional"))
      (node (ref "R84") (pin "P$2") (pinfunction "S_P$2") (pintype "passive"))
    )
    (net (code "65") (name "Net-(IC3A-X6)") (class "Default")
      (node (ref "IC3") (pin "2") (pinfunction "X6_2") (pintype "bidirectional"))
      (node (ref "R85") (pin "P$2") (pinfunction "S_P$2") (pintype "passive"))
    )
    (net (code "66") (name "Net-(IC3A-X7)") (class "Default")
      (node (ref "IC3") (pin "4") (pinfunction "X7_4") (pintype "bidirectional"))
      (node (ref "R89") (pin "P$2") (pinfunction "S_P$2") (pintype "passive"))
    )
    (net (code "67") (name "Net-(IC5-PF0{slash}OSC_IN{slash}I2C2_SDA)") (class "Default")
      (node (ref "IC5") (pin "5") (pinfunction "PF0/OSC_IN/I2C2_SDA_5") (pintype "bidirectional"))
      (node (ref "R9") (pin "1") (pinfunction "1_1") (pintype "passive"))
    )
    (net (code "68") (name "Net-(IC5-PF1{slash}OSC_OUT{slash}I2C2_SCL)") (class "Default")
      (node (ref "IC5") (pin "6") (pinfunction "PF1/OSC_OUT/I2C2_SCL_6") (pintype "bidirectional"))
      (node (ref "R8") (pin "1") (pinfunction "1_1") (pintype "passive"))
    )
    (net (code "69") (name "Net-(IC6A-X0)") (class "Default")
      (node (ref "IC6") (pin "13") (pinfunction "X0_13") (pintype "bidirectional"))
      (node (ref "R81") (pin "2") (pinfunction "S_2") (pintype "passive"))
    )
    (net (code "70") (name "Net-(IC6A-X1)") (class "Default")
      (node (ref "IC6") (pin "14") (pinfunction "X1_14") (pintype "bidirectional"))
      (node (ref "R80") (pin "2") (pinfunction "S_2") (pintype "passive"))
    )
    (net (code "71") (name "Net-(IC6A-X2)") (class "Default")
      (node (ref "IC6") (pin "15") (pinfunction "X2_15") (pintype "bidirectional"))
      (node (ref "R79") (pin "2") (pinfunction "S_2") (pintype "passive"))
    )
    (net (code "72") (name "Net-(IC6A-X3)") (class "Default")
      (node (ref "IC6") (pin "12") (pinfunction "X3_12") (pintype "bidirectional"))
      (node (ref "R82") (pin "2") (pinfunction "S_2") (pintype "passive"))
    )
    (net (code "73") (name "Net-(IC6A-X4)") (class "Default")
      (node (ref "IC6") (pin "1") (pinfunction "X4_1") (pintype "bidirectional"))
      (node (ref "R78") (pin "2") (pinfunction "S_2") (pintype "passive"))
    )
    (net (code "74") (name "Net-(IC6A-X6)") (class "Default")
      (node (ref "IC6") (pin "2") (pinfunction "X6_2") (pintype "bidirectional"))
      (node (ref "R83") (pin "2") (pinfunction "S_2") (pintype "passive"))
    )
    (net (code "75") (name "Net-(IC7-VI)") (class "Default")
      (node (ref "C23") (pin "1") (pinfunction "1_1") (pintype "passive"))
      (node (ref "IC7") (pin "3") (pinfunction "VI_3") (pintype "input"))
      (node (ref "L4") (pin "1") (pinfunction "1_1") (pintype "passive"))
    )
    (net (code "76") (name "Net-(IC8A--IN)") (class "Default")
      (node (ref "C28") (pin "1") (pinfunction "1_1") (pintype "passive"))
      (node (ref "IC8") (pin "2") (pinfunction "-IN_2") (pintype "input"))
      (node (ref "R20") (pin "2") (pinfunction "2_2") (pintype "passive"))
      (node (ref "R23") (pin "1") (pinfunction "1_1") (pintype "passive"))
      (node (ref "R32") (pin "1") (pinfunction "1_1") (pintype "passive"))
    )
    (net (code "77") (name "Net-(IC8B--IN)") (class "Default")
      (node (ref "C27") (pin "1") (pinfunction "1_1") (pintype "passive"))
      (node (ref "IC8") (pin "6") (pinfunction "-IN_6") (pintype "input"))
      (node (ref "R19") (pin "2") (pinfunction "2_2") (pintype "passive"))
      (node (ref "R24") (pin "1") (pinfunction "1_1") (pintype "passive"))
      (node (ref "R31") (pin "1") (pinfunction "1_1") (pintype "passive"))
    )
    (net (code "78") (name "Net-(IC9A--IN)") (class "Default")
      (node (ref "C29") (pin "1") (pinfunction "1_1") (pintype "passive"))
      (node (ref "IC9") (pin "2") (pinfunction "-IN_2") (pintype "input"))
      (node (ref "R15") (pin "2") (pinfunction "2_2") (pintype "passive"))
      (node (ref "R22") (pin "1") (pinfunction "1_1") (pintype "passive"))
      (node (ref "R25") (pin "1") (pinfunction "1_1") (pintype "passive"))
    )
    (net (code "79") (name "Net-(IC9B--IN)") (class "Default")
      (node (ref "C31") (pin "1") (pinfunction "1_1") (pintype "passive"))
      (node (ref "IC9") (pin "6") (pinfunction "-IN_6") (pintype "input"))
      (node (ref "R13") (pin "2") (pinfunction "2_2") (pintype "passive"))
      (node (ref "R26") (pin "1") (pinfunction "1_1") (pintype "passive"))
      (node (ref "R27") (pin "1") (pinfunction "1_1") (pintype "passive"))
    )
    (net (code "80") (name "Net-(IC10A--IN)") (class "Default")
      (node (ref "C32") (pin "1") (pinfunction "1_1") (pintype "passive"))
      (node (ref "IC10") (pin "2") (pinfunction "-IN_2") (pintype "input"))
      (node (ref "R14") (pin "2") (pinfunction "2_2") (pintype "passive"))
      (node (ref "R21") (pin "1") (pinfunction "1_1") (pintype "passive"))
      (node (ref "R28") (pin "1") (pinfunction "1_1") (pintype "passive"))
    )
    (net (code "81") (name "Net-(IC10B--IN)") (class "Default")
      (node (ref "C35") (pin "1") (pinfunction "1_1") (pintype "passive"))
      (node (ref "IC10") (pin "6") (pinfunction "-IN_6") (pintype "input"))
      (node (ref "R16") (pin "2") (pinfunction "2_2") (pintype "passive"))
      (node (ref "R29") (pin "1") (pinfunction "1_1") (pintype "passive"))
      (node (ref "R30") (pin "1") (pinfunction "1_1") (pintype "passive"))
    )
    (net (code "82") (name "Net-(IC12A--IN)") (class "Default")
      (node (ref "C44") (pin "1") (pinfunction "1_1") (pintype "passive"))
      (node (ref "IC12") (pin "2") (pinfunction "-IN_2") (pintype "input"))
      (node (ref "R41") (pin "2") (pinfunction "2_2") (pintype "passive"))
      (node (ref "R47") (pin "1") (pinfunction "1_1") (pintype "passive"))
    )
    (net (code "83") (name "Net-(IC12A-OUT)") (class "Default")
      (node (ref "C44") (pin "2") (pinfunction "2_2") (pintype "passive"))
      (node (ref "IC12") (pin "1") (pinfunction "OUT_1") (pintype "output"))
      (node (ref "IC12") (pin "5") (pinfunction "+IN_5") (pintype "input"))
      (node (ref "R35") (pin "2") (pinfunction "2_2") (pintype "passive"))
    )
    (net (code "84") (name "Net-(IC12B--IN)") (class "Default")
      (node (ref "IC12") (pin "6") (pinfunction "-IN_6") (pintype "input"))
      (node (ref "LED4") (pin "2") (pinfunction "2_2") (pintype "bidirectional"))
      (node (ref "R54") (pin "1") (pinfunction "1_1") (pintype "passive"))
    )
    (net (code "85") (name "Net-(IC12B-OUT)") (class "Default")
      (node (ref "IC12") (pin "7") (pinfunction "OUT_7") (pintype "output"))
      (node (ref "LED4") (pin "1") (pinfunction "1_1") (pintype "bidirectional"))
    )
    (net (code "86") (name "Net-(IC12C-+IN)") (class "Default")
      (node (ref "C45") (pin "2") (pinfunction "2_2") (pintype "passive"))
      (node (ref "IC12") (pin "10") (pinfunction "+IN_10") (pintype "input"))
      (node (ref "IC12") (pin "14") (pinfunction "OUT_14") (pintype "output"))
      (node (ref "R34") (pin "2") (pinfunction "2_2") (pintype "passive"))
    )
    (net (code "87") (name "Net-(IC12C--IN)") (class "Default")
      (node (ref "IC12") (pin "9") (pinfunction "-IN_9") (pintype "input"))
      (node (ref "LED6") (pin "2") (pinfunction "2_2") (pintype "bidirectional"))
      (node (ref "R55") (pin "1") (pinfunction "1_1") (pintype "passive"))
    )
    (net (code "88") (name "Net-(IC12C-OUT)") (class "Default")
      (node (ref "IC12") (pin "8") (pinfunction "OUT_8") (pintype "output"))
      (node (ref "LED6") (pin "1") (pinfunction "1_1") (pintype "bidirectional"))
    )
    (net (code "89") (name "Net-(IC12D--IN)") (class "Default")
      (node (ref "C45") (pin "1") (pinfunction "1_1") (pintype "passive"))
      (node (ref "IC12") (pin "13") (pinfunction "-IN_13") (pintype "input"))
      (node (ref "R42") (pin "2") (pinfunction "2_2") (pintype "passive"))
      (node (ref "R50") (pin "1") (pinfunction "1_1") (pintype "passive"))
    )
    (net (code "90") (name "Net-(IC13A--IN)") (class "Default")
      (node (ref "C46") (pin "1") (pinfunction "1_1") (pintype "passive"))
      (node (ref "IC13") (pin "2") (pinfunction "-IN_2") (pintype "input"))
      (node (ref "R43") (pin "2") (pinfunction "2_2") (pintype "passive"))
      (node (ref "R49") (pin "1") (pinfunction "1_1") (pintype "passive"))
    )
    (net (code "91") (name "Net-(IC13A-OUT)") (class "Default")
      (node (ref "C46") (pin "2") (pinfunction "2_2") (pintype "passive"))
      (node (ref "IC13") (pin "1") (pinfunction "OUT_1") (pintype "output"))
      (node (ref "IC13") (pin "5") (pinfunction "+IN_5") (pintype "input"))
      (node (ref "R36") (pin "2") (pinfunction "2_2") (pintype "passive"))
    )
    (net (code "92") (name "Net-(IC13B--IN)") (class "Default")
      (node (ref "IC13") (pin "6") (pinfunction "-IN_6") (pintype "input"))
      (node (ref "LED3") (pin "2") (pinfunction "2_2") (pintype "bidirectional"))
      (node (ref "R56") (pin "1") (pinfunction "1_1") (pintype "passive"))
    )
    (net (code "93") (name "Net-(IC13B-OUT)") (class "Default")
      (node (ref "IC13") (pin "7") (pinfunction "OUT_7") (pintype "output"))
      (node (ref "LED3") (pin "1") (pinfunction "1_1") (pintype "bidirectional"))
    )
    (net (code "94") (name "Net-(IC13C-+IN)") (class "Default")
      (node (ref "C47") (pin "2") (pinfunction "2_2") (pintype "passive"))
      (node (ref "IC13") (pin "10") (pinfunction "+IN_10") (pintype "input"))
      (node (ref "IC13") (pin "14") (pinfunction "OUT_14") (pintype "output"))
      (node (ref "R38") (pin "2") (pinfunction "2_2") (pintype "passive"))
    )
    (net (code "95") (name "Net-(IC13C--IN)") (class "Default")
      (node (ref "IC13") (pin "9") (pinfunction "-IN_9") (pintype "input"))
      (node (ref "LED2") (pin "2") (pinfunction "2_2") (pintype "bidirectional"))
      (node (ref "R57") (pin "1") (pinfunction "1_1") (pintype "passive"))
    )
    (net (code "96") (name "Net-(IC13C-OUT)") (class "Default")
      (node (ref "IC13") (pin "8") (pinfunction "OUT_8") (pintype "output"))
      (node (ref "LED2") (pin "1") (pinfunction "1_1") (pintype "bidirectional"))
    )
    (net (code "97") (name "Net-(IC13D--IN)") (class "Default")
      (node (ref "C47") (pin "1") (pinfunction "1_1") (pintype "passive"))
      (node (ref "IC13") (pin "13") (pinfunction "-IN_13") (pintype "input"))
      (node (ref "R44") (pin "2") (pinfunction "2_2") (pintype "passive"))
      (node (ref "R53") (pin "1") (pinfunction "1_1") (pintype "passive"))
    )
    (net (code "98") (name "Net-(IC14A--IN)") (class "Default")
      (node (ref "C48") (pin "1") (pinfunction "1_1") (pintype "passive"))
      (node (ref "IC14") (pin "2") (pinfunction "-IN_2") (pintype "input"))
      (node (ref "R45") (pin "2") (pinfunction "2_2") (pintype "passive"))
      (node (ref "R51") (pin "1") (pinfunction "1_1") (pintype "passive"))
    )
    (net (code "99") (name "Net-(IC14A-OUT)") (class "Default")
      (node (ref "C48") (pin "2") (pinfunction "2_2") (pintype "passive"))
      (node (ref "IC14") (pin "1") (pinfunction "OUT_1") (pintype "output"))
      (node (ref "IC14") (pin "5") (pinfunction "+IN_5") (pintype "input"))
      (node (ref "R37") (pin "2") (pinfunction "2_2") (pintype "passive"))
    )
    (net (code "100") (name "Net-(IC14B--IN)") (class "Default")
      (node (ref "IC14") (pin "6") (pinfunction "-IN_6") (pintype "input"))
      (node (ref "LED5") (pin "2") (pinfunction "2_2") (pintype "bidirectional"))
      (node (ref "R58") (pin "1") (pinfunction "1_1") (pintype "passive"))
    )
    (net (code "101") (name "Net-(IC14B-OUT)") (class "Default")
      (node (ref "IC14") (pin "7") (pinfunction "OUT_7") (pintype "output"))
      (node (ref "LED5") (pin "1") (pinfunction "1_1") (pintype "bidirectional"))
    )
    (net (code "102") (name "Net-(IC14C-+IN)") (class "Default")
      (node (ref "C49") (pin "2") (pinfunction "2_2") (pintype "passive"))
      (node (ref "IC14") (pin "10") (pinfunction "+IN_10") (pintype "input"))
      (node (ref "IC14") (pin "14") (pinfunction "OUT_14") (pintype "output"))
      (node (ref "R39") (pin "2") (pinfunction "2_2") (pintype "passive"))
    )
    (net (code "103") (name "Net-(IC14C--IN)") (class "Default")
      (node (ref "IC14") (pin "9") (pinfunction "-IN_9") (pintype "input"))
      (node (ref "LED1") (pin "2") (pinfunction "2_2") (pintype "bidirectional"))
      (node (ref "R59") (pin "1") (pinfunction "1_1") (pintype "passive"))
    )
    (net (code "104") (name "Net-(IC14C-OUT)") (class "Default")
      (node (ref "IC14") (pin "8") (pinfunction "OUT_8") (pintype "output"))
      (node (ref "LED1") (pin "1") (pinfunction "1_1") (pintype "bidirectional"))
    )
    (net (code "105") (name "Net-(IC14D--IN)") (class "Default")
      (node (ref "C49") (pin "1") (pinfunction "1_1") (pintype "passive"))
      (node (ref "IC14") (pin "13") (pinfunction "-IN_13") (pintype "input"))
      (node (ref "R46") (pin "2") (pinfunction "2_2") (pintype "passive"))
      (node (ref "R52") (pin "1") (pinfunction "1_1") (pintype "passive"))
    )
    (net (code "106") (name "Net-(J1-3)") (class "Default")
      (node (ref "J1") (pin "P3") (pinfunction "3_P3") (pintype "passive"))
      (node (ref "R39") (pin "1") (pinfunction "1_1") (pintype "passive"))
      (node (ref "R46") (pin "1") (pinfunction "1_1") (pintype "passive"))
    )
    (net (code "107") (name "Net-(J2-3)") (class "Default")
      (node (ref "J2") (pin "P3") (pinfunction "3_P3") (pintype "passive"))
      (node (ref "R37") (pin "1") (pinfunction "1_1") (pintype "passive"))
      (node (ref "R45") (pin "1") (pinfunction "1_1") (pintype "passive"))
    )
    (net (code "108") (name "Net-(J3-3)") (class "Default")
      (node (ref "J3") (pin "P3") (pinfunction "3_P3") (pintype "passive"))
      (node (ref "R38") (pin "1") (pinfunction "1_1") (pintype "passive"))
      (node (ref "R44") (pin "1") (pinfunction "1_1") (pintype "passive"))
    )
    (net (code "109") (name "Net-(J4-3)") (class "Default")
      (node (ref "J4") (pin "P3") (pinfunction "3_P3") (pintype "passive"))
      (node (ref "R36") (pin "1") (pinfunction "1_1") (pintype "passive"))
      (node (ref "R43") (pin "1") (pinfunction "1_1") (pintype "passive"))
    )
    (net (code "110") (name "Net-(J5-3)") (class "Default")
      (node (ref "J5") (pin "P3") (pinfunction "3_P3") (pintype "passive"))
      (node (ref "R34") (pin "1") (pinfunction "1_1") (pintype "passive"))
      (node (ref "R42") (pin "1") (pinfunction "1_1") (pintype "passive"))
    )
    (net (code "111") (name "Net-(J6-3)") (class "Default")
      (node (ref "J6") (pin "P3") (pinfunction "3_P3") (pintype "passive"))
      (node (ref "R35") (pin "1") (pinfunction "1_1") (pintype "passive"))
      (node (ref "R41") (pin "1") (pinfunction "1_1") (pintype "passive"))
    )
    (net (code "112") (name "Net-(J7-2)") (class "Default")
      (node (ref "J7") (pin "P2") (pinfunction "2_P2") (pintype "passive"))
      (node (ref "R65") (pin "2") (pinfunction "2_2") (pintype "passive"))
    )
    (net (code "113") (name "Net-(J7-3)") (class "Default")
      (node (ref "J7") (pin "P3") (pinfunction "3_P3") (pintype "passive"))
      (node (ref "R66") (pin "1") (pinfunction "1_1") (pintype "passive"))
    )
    (net (code "114") (name "Net-(J8-2)") (class "Default")
      (node (ref "J8") (pin "P2") (pinfunction "2_P2") (pintype "passive"))
      (node (ref "R62") (pin "2") (pinfunction "2_2") (pintype "passive"))
    )
    (net (code "115") (name "Net-(J8-3)") (class "Default")
      (node (ref "J8") (pin "P3") (pinfunction "3_P3") (pintype "passive"))
      (node (ref "R77") (pin "1") (pinfunction "1_1") (pintype "passive"))
    )
    (net (code "116") (name "Net-(J9-2)") (class "Default")
      (node (ref "J9") (pin "P2") (pinfunction "2_P2") (pintype "passive"))
      (node (ref "R63") (pin "2") (pinfunction "2_2") (pintype "passive"))
    )
    (net (code "117") (name "Net-(J9-3)") (class "Default")
      (node (ref "J9") (pin "P3") (pinfunction "3_P3") (pintype "passive"))
      (node (ref "R68") (pin "1") (pinfunction "1_1") (pintype "passive"))
    )
    (net (code "118") (name "Net-(J10-2)") (class "Default")
      (node (ref "J10") (pin "P2") (pinfunction "2_P2") (pintype "passive"))
      (node (ref "R61") (pin "2") (pinfunction "2_2") (pintype "passive"))
    )
    (net (code "119") (name "Net-(J10-3)") (class "Default")
      (node (ref "J10") (pin "P3") (pinfunction "3_P3") (pintype "passive"))
      (node (ref "R76") (pin "1") (pinfunction "1_1") (pintype "passive"))
    )
    (net (code "120") (name "Net-(J11-2)") (class "Default")
      (node (ref "J11") (pin "P2") (pinfunction "2_P2") (pintype "passive"))
      (node (ref "R64") (pin "2") (pinfunction "2_2") (pintype "passive"))
    )
    (net (code "121") (name "Net-(J11-3)") (class "Default")
      (node (ref "J11") (pin "P3") (pinfunction "3_P3") (pintype "passive"))
      (node (ref "R67") (pin "1") (pinfunction "1_1") (pintype "passive"))
    )
    (net (code "122") (name "Net-(J12-2)") (class "Default")
      (node (ref "J12") (pin "P2") (pinfunction "2_P2") (pintype "passive"))
      (node (ref "R60") (pin "2") (pinfunction "2_2") (pintype "passive"))
    )
    (net (code "123") (name "Net-(J12-3)") (class "Default")
      (node (ref "J12") (pin "P3") (pinfunction "3_P3") (pintype "passive"))
      (node (ref "R75") (pin "1") (pinfunction "1_1") (pintype "passive"))
    )
    (net (code "124") (name "Net-(J13-3)") (class "Default")
      (node (ref "C38") (pin "1") (pinfunction "1_1") (pintype "passive"))
      (node (ref "J13") (pin "P3") (pinfunction "3_P3") (pintype "passive"))
      (node (ref "R30") (pin "2") (pinfunction "2_2") (pintype "passive"))
    )
    (net (code "125") (name "Net-(J14-3)") (class "Default")
      (node (ref "C39") (pin "1") (pinfunction "1_1") (pintype "passive"))
      (node (ref "J14") (pin "P3") (pinfunction "3_P3") (pintype "passive"))
      (node (ref "R28") (pin "2") (pinfunction "2_2") (pintype "passive"))
    )
    (net (code "126") (name "Net-(J15-3)") (class "Default")
      (node (ref "C37") (pin "1") (pinfunction "1_1") (pintype "passive"))
      (node (ref "J15") (pin "P3") (pinfunction "3_P3") (pintype "passive"))
      (node (ref "R27") (pin "2") (pinfunction "2_2") (pintype "passive"))
    )
    (net (code "127") (name "Net-(J16-3)") (class "Default")
      (node (ref "C40") (pin "1") (pinfunction "1_1") (pintype "passive"))
      (node (ref "J16") (pin "P3") (pinfunction "3_P3") (pintype "passive"))
      (node (ref "R25") (pin "2") (pinfunction "2_2") (pintype "passive"))
    )
    (net (code "128") (name "Net-(J17-3)") (class "Default")
      (node (ref "C36") (pin "1") (pinfunction "1_1") (pintype "passive"))
      (node (ref "J17") (pin "P3") (pinfunction "3_P3") (pintype "passive"))
      (node (ref "R31") (pin "2") (pinfunction "2_2") (pintype "passive"))
    )
    (net (code "129") (name "Net-(J18-3)") (class "Default")
      (node (ref "C42") (pin "1") (pinfunction "1_1") (pintype "passive"))
      (node (ref "J18") (pin "P3") (pinfunction "3_P3") (pintype "passive"))
      (node (ref "R32") (pin "2") (pinfunction "2_2") (pintype "passive"))
    )
    (net (code "130") (name "Net-(JP3-Pad2)") (class "Default")
      (node (ref "JP3") (pin "2") (pinfunction "2_2") (pintype "passive"))
      (node (ref "R5") (pin "2") (pinfunction "2_2") (pintype "passive"))
    )
    (net (code "131") (name "Net-(JP3-Pad3)") (class "Default")
      (node (ref "JP3") (pin "3") (pinfunction "3_3") (pintype "passive"))
      (node (ref "R7") (pin "2") (pinfunction "2_2") (pintype "passive"))
    )
    (net (code "132") (name "Net-(JP4-Pad2)") (class "Default")
      (node (ref "JP4") (pin "2") (pinfunction "2_2") (pintype "passive"))
      (node (ref "R10") (pin "2") (pinfunction "2_2") (pintype "passive"))
    )
    (net (code "133") (name "Net-(JP4-Pad3)") (class "Default")
      (node (ref "JP4") (pin "3") (pinfunction "3_3") (pintype "passive"))
      (node (ref "R11") (pin "2") (pinfunction "2_2") (pintype "passive"))
    )
    (net (code "134") (name "Net-(Q1B-2)") (class "Default")
      (node (ref "C4") (pin "2") (pinfunction "2_2") (pintype "passive"))
      (node (ref "Q1") (pin "3") (pinfunction "2_3") (pintype "passive"))
      (node (ref "R8") (pin "2") (pinfunction "2_2") (pintype "passive"))
    )
    (net (code "135") (name "Net-(R78A-A)") (class "Default")
      (node (ref "R17") (pin "1") (pinfunction "1_1") (pintype "passive"))
      (node (ref "R78") (pin "B") (pinfunction "A_B") (pintype "passive"))
    )
    (net (code "136") (name "Net-(R79A-A)") (class "Default")
      (node (ref "R3") (pin "1") (pinfunction "1_1") (pintype "passive"))
      (node (ref "R79") (pin "B") (pinfunction "A_B") (pintype "passive"))
    )
    (net (code "137") (name "Net-(R80A-A)") (class "Default")
      (node (ref "R1") (pin "1") (pinfunction "1_1") (pintype "passive"))
      (node (ref "R80") (pin "B") (pinfunction "A_B") (pintype "passive"))
    )
    (net (code "138") (name "Net-(R81A-A)") (class "Default")
      (node (ref "R2") (pin "1") (pinfunction "1_1") (pintype "passive"))
      (node (ref "R81") (pin "B") (pinfunction "A_B") (pintype "passive"))
    )
    (net (code "139") (name "Net-(R82A-A)") (class "Default")
      (node (ref "R4") (pin "1") (pinfunction "1_1") (pintype "passive"))
      (node (ref "R82") (pin "B") (pinfunction "A_B") (pintype "passive"))
    )
    (net (code "140") (name "Net-(R83A-A)") (class "Default")
      (node (ref "R18") (pin "1") (pinfunction "1_1") (pintype "passive"))
      (node (ref "R83") (pin "B") (pinfunction "A_B") (pintype "passive"))
    )
    (net (code "141") (name "POTS_ADDR_A") (class "Default")
      (node (ref "IC3") (pin "9") (pinfunction "C_9") (pintype "input"))
      (node (ref "IC5") (pin "21") (pinfunction "PA5/SPI1_SCK/I2S1_CK/TIM2_CH1/ADC_IN5/DAC1_OUT2_21") (pintype "bidirectional"))
      (node (ref "IC6") (pin "11") (pinfunction "A_11") (pintype "input"))
    )
    (net (code "142") (name "POTS_ADDR_B") (class "Default")
      (node (ref "IC3") (pin "10") (pinfunction "B_10") (pintype "input"))
      (node (ref "IC5") (pin "20") (pinfunction "PA4/SPI1_NSS/I2S1_WS/SPI3_NSS/I2S3_WS/USART2_CK/TIM3_CH2/ADC_IN4/DAC1_OUT1_20") (pintype "bidirectional"))
      (node (ref "IC6") (pin "10") (pinfunction "B_10") (pintype "input"))
    )
    (net (code "143") (name "POTS_ADDR_C") (class "Default")
      (node (ref "IC3") (pin "11") (pinfunction "A_11") (pintype "input"))
      (node (ref "IC5") (pin "18") (pinfunction "PA3/SPI3_MOSI/I2S3_SD/USART2_RX/TIM2_CH4/TIM5_CH4/ADC_IN3_18") (pintype "bidirectional"))
      (node (ref "IC6") (pin "9") (pinfunction "C_9") (pintype "input"))
    )
    (net (code "144") (name "RESET") (class "Default")
      (node (ref "IC5") (pin "7") (pinfunction "NRST_7") (pintype "bidirectional"))
      (node (ref "JP6") (pin "4") (pinfunction "4_4") (pintype "passive"))
      (node (ref "R12") (pin "1") (pinfunction "1_1") (pintype "passive"))
    )
    (net (code "145") (name "RIGHT_RX") (class "Default")
      (node (ref "IC5") (pin "25") (pinfunction "PC5/USART1_RX/ADC_IN15_25") (pintype "bidirectional"))
      (node (ref "R10") (pin "1") (pinfunction "1_1") (pintype "passive"))
    )
    (net (code "146") (name "RIGHT_TX") (class "Default")
      (node (ref "IC5") (pin "24") (pinfunction "PC4/USART1_TX/ADC_IN14_24") (pintype "bidirectional"))
      (node (ref "R11") (pin "1") (pinfunction "1_1") (pintype "passive"))
    )
    (net (code "147") (name "STAGE_LED_1") (class "Default")
      (node (ref "IC5") (pin "45") (pinfunction "PA12/SPI1_SCK/I2S1_CK/USART1_RTS/CAN_TX/TIM4_CH2/TIM5_CH3_45") (pintype "bidirectional"))
      (node (ref "R17") (pin "2") (pinfunction "2_2") (pintype "passive"))
    )
    (net (code "148") (name "STAGE_LED_2") (class "Default")
      (node (ref "IC5") (pin "2") (pinfunction "PC13/TIMESTAMP/RTC_TAMPER1_2") (pintype "bidirectional"))
      (node (ref "R3") (pin "2") (pinfunction "2_2") (pintype "passive"))
    )
    (net (code "149") (name "STAGE_LED_3") (class "Default")
      (node (ref "IC5") (pin "3") (pinfunction "PC14/OSC32_IN_3") (pintype "bidirectional"))
      (node (ref "R1") (pin "2") (pinfunction "2_2") (pintype "passive"))
    )
    (net (code "150") (name "STAGE_LED_4") (class "Default")
      (node (ref "IC5") (pin "4") (pinfunction "PC15/OSC32_OUT_4") (pintype "bidirectional"))
      (node (ref "R2") (pin "2") (pinfunction "2_2") (pintype "passive"))
    )
    (net (code "151") (name "STAGE_LED_5") (class "Default")
      (node (ref "IC5") (pin "16") (pinfunction "PA2/SPI3_MISO/I2S3_MCK/USART2_TX/TIM2_CH3/TIM5_CH3/ADC_IN2_16") (pintype "bidirectional"))
      (node (ref "R4") (pin "2") (pinfunction "2_2") (pintype "passive"))
    )
    (net (code "152") (name "STAGE_LED_6") (class "Default")
      (node (ref "IC5") (pin "28") (pinfunction "PB2/SDADC_AIN4P/SDADC2_AIN6P_28") (pintype "bidirectional"))
      (node (ref "R18") (pin "2") (pinfunction "2_2") (pintype "passive"))
    )
    (net (code "153") (name "SWCLK") (class "Default")
      (node (ref "IC5") (pin "49") (pinfunction "PA14/I2C1_SDA/JTCK-SWCLK_49") (pintype "bidirectional"))
      (node (ref "JP6") (pin "3") (pinfunction "3_3") (pintype "passive"))
    )
    (net (code "154") (name "SWDIO") (class "Default")
      (node (ref "IC5") (pin "46") (pinfunction "PA13/SPI1_MISO/I2S1_MCK/USART3_CTS/TIM4_CH3/TIM5_CH4/JTMS-SWDIO_46") (pintype "bidirectional"))
      (node (ref "JP6") (pin "2") (pinfunction "2_2") (pintype "passive"))
    )
    (net (code "155") (name "SW_MODE_1") (class "Default")
      (node (ref "IC5") (pin "8") (pinfunction "PC0/TIM5_CH1/ADC_IN10_8") (pintype "bidirectional"))
      (node (ref "SW1") (pin "3") (pinfunction "3_3") (pintype "passive"))
      (node (ref "SW1") (pin "4") (pinfunction "4_4") (pintype "passive"))
    )
    (net (code "156") (name "SW_MODE_2") (class "Default")
      (node (ref "IC5") (pin "9") (pinfunction "PC1/TIM5_CH2/ADC_IN11_9") (pintype "bidirectional"))
      (node (ref "SW2") (pin "3") (pinfunction "3_3") (pintype "passive"))
      (node (ref "SW2") (pin "4") (pinfunction "4_4") (pintype "passive"))
    )
    (net (code "157") (name "SW_MODE_3") (class "Default")
      (node (ref "IC5") (pin "10") (pinfunction "PC2/SPI2_MISO/I2S2_MCK/TIM5_CH3/ADC_IN12_10") (pintype "bidirectional"))
      (node (ref "SW3") (pin "3") (pinfunction "3_3") (pintype "passive"))
      (node (ref "SW3") (pin "4") (pinfunction "4_4") (pintype "passive"))
    )
    (net (code "158") (name "SW_MODE_4") (class "Default")
      (node (ref "IC5") (pin "11") (pinfunction "PC3/SPI2_MOSI/I2S2_SD/TIM5_CH4/ADC_IN13_11") (pintype "bidirectional"))
      (node (ref "SW4") (pin "3") (pinfunction "3_3") (pintype "passive"))
      (node (ref "SW4") (pin "4") (pinfunction "4_4") (pintype "passive"))
    )
    (net (code "159") (name "SW_MODE_5") (class "Default")
      (node (ref "IC5") (pin "14") (pinfunction "PA0/USART2_CTS/TIM2_CH1/TIM5_CH1/ADC_IN0_14") (pintype "bidirectional"))
      (node (ref "SW5") (pin "3") (pinfunction "3_3") (pintype "passive"))
      (node (ref "SW5") (pin "4") (pinfunction "4_4") (pintype "passive"))
    )
    (net (code "160") (name "SW_MODE_6") (class "Default")
      (node (ref "IC5") (pin "15") (pinfunction "PA1/SPI3_SCK/I2S3_CK/USART2_RTS/TIM2_CH2/TIM5_CH2/ADC_IN1_15") (pintype "bidirectional"))
      (node (ref "SW6") (pin "3") (pinfunction "3_3") (pintype "passive"))
      (node (ref "SW6") (pin "4") (pinfunction "4_4") (pintype "passive"))
    )
    (net (code "161") (name "VCC") (class "Default")
      (node (ref "C21") (pin "1") (pinfunction "1_1") (pintype "passive"))
      (node (ref "C25") (pin "1") (pinfunction "1_1") (pintype "passive"))
      (node (ref "C50") (pin "1") (pinfunction "1_1") (pintype "passive"))
      (node (ref "C52") (pin "1") (pinfunction "1_1") (pintype "passive"))
      (node (ref "C54") (pin "1") (pinfunction "1_1") (pintype "passive"))
      (node (ref "IC12") (pin "4") (pinfunction "V+_4") (pintype "power_in"))
      (node (ref "IC13") (pin "4") (pinfunction "V+_4") (pintype "power_in"))
      (node (ref "IC14") (pin "4") (pinfunction "V+_4") (pintype "power_in"))
      (node (ref "L5") (pin "1") (pinfunction "1_1") (pintype "passive"))
    )
    (net (code "162") (name "VEE") (class "Default")
      (node (ref "C1") (pin "2") (pinfunction "2_2") (pintype "passive"))
      (node (ref "C2") (pin "2") (pinfunction "2_2") (pintype "passive"))
      (node (ref "C51") (pin "2") (pinfunction "2_2") (pintype "passive"))
      (node (ref "C53") (pin "2") (pinfunction "2_2") (pintype "passive"))
      (node (ref "C55") (pin "2") (pinfunction "2_2") (pintype "passive"))
      (node (ref "IC12") (pin "11") (pinfunction "V-_11") (pintype "power_in"))
      (node (ref "IC13") (pin "11") (pinfunction "V-_11") (pintype "power_in"))
      (node (ref "IC14") (pin "11") (pinfunction "V-_11") (pintype "power_in"))
      (node (ref "L1") (pin "1") (pinfunction "1_1") (pintype "passive"))
      (node (ref "R33") (pin "1") (pinfunction "1_1") (pintype "passive"))
    )
    (net (code "163") (name "VREF_BIAS") (class "Default")
      (node (ref "C43") (pin "1") (pinfunction "1_1") (pintype "passive"))
      (node (ref "IC12") (pin "12") (pinfunction "+IN_12") (pintype "input"))
      (node (ref "IC12") (pin "3") (pinfunction "+IN_3") (pintype "input"))
      (node (ref "IC13") (pin "12") (pinfunction "+IN_12") (pintype "input"))
      (node (ref "IC13") (pin "3") (pinfunction "+IN_3") (pintype "input"))
      (node (ref "IC14") (pin "12") (pinfunction "+IN_12") (pintype "input"))
      (node (ref "IC14") (pin "3") (pinfunction "+IN_3") (pintype "input"))
      (node (ref "R40") (pin "1") (pinfunction "1_1") (pintype "passive"))
      (node (ref "R48") (pin "2") (pinfunction "2_2") (pintype "passive"))
    )
    (net (code "164") (name "unconnected-(IC1-OUT0-Pad5)") (class "Default")
      (node (ref "IC1") (pin "5") (pinfunction "OUT0_5") (pintype "bidirectional"))
    )
    (net (code "165") (name "unconnected-(IC1-OUT1-Pad6)") (class "Default")
      (node (ref "IC1") (pin "6") (pinfunction "OUT1_6") (pintype "bidirectional"))
    )
    (net (code "166") (name "unconnected-(IC1-OUT14-Pad19)") (class "Default")
      (node (ref "IC1") (pin "19") (pinfunction "OUT14_19") (pintype "bidirectional"))
    )
    (net (code "167") (name "unconnected-(IC1-OUT15-Pad20)") (class "Default")
      (node (ref "IC1") (pin "20") (pinfunction "OUT15_20") (pintype "bidirectional"))
    )
    (net (code "168") (name "unconnected-(IC1-SOUT-Pad22)") (class "Default")
      (node (ref "IC1") (pin "22") (pinfunction "SOUT_22") (pintype "bidirectional"))
    )
    (net (code "169") (name "unconnected-(IC2-EN-Pad4)") (class "Default")
      (node (ref "IC2") (pin "4") (pinfunction "EN_4") (pintype "input"))
    )
    (net (code "170") (name "unconnected-(IC3A-X0-Pad13)") (class "Default")
      (node (ref "IC3") (pin "13") (pinfunction "X0_13") (pintype "bidirectional"))
    )
    (net (code "171") (name "unconnected-(IC3A-X3-Pad12)") (class "Default")
      (node (ref "IC3") (pin "12") (pinfunction "X3_12") (pintype "bidirectional"))
    )
    (net (code "172") (name "unconnected-(IC4-VOUTF-Pad9)") (class "Default")
      (node (ref "IC4") (pin "9") (pinfunction "VOUTF_9") (pintype "output"))
    )
    (net (code "173") (name "unconnected-(IC4-VOUTH-Pad8)") (class "Default")
      (node (ref "IC4") (pin "8") (pinfunction "VOUTH_8") (pintype "output"))
    )
    (net (code "174") (name "unconnected-(IC5-PB3{slash}SPI1_SCK{slash}I2S1_CK{slash}SPI3_SCK{slash}I2S3_CK{slash}USART2_TX{slash}TIM2_CH2{slash}JTDO{slash}SPI3_SCK{slash}JTDO-Pad55)") (class "Default")
      (node (ref "IC5") (pin "55") (pinfunction "PB3/SPI1_SCK/I2S1_CK/SPI3_SCK/I2S3_CK/USART2_TX/TIM2_CH2/JTDO/SPI3_SCK/JTDO_55") (pintype "bidirectional"))
    )
    (net (code "175") (name "unconnected-(IC5-PB4{slash}SPI1_MISO{slash}I2S1_MCK{slash}SPI3_MISO{slash}I2S3_MCK{slash}USART2_RX{slash}TIM3_CH1{slash}NJTRST-Pad56)") (class "Default")
      (node (ref "IC5") (pin "56") (pinfunction "PB4/SPI1_MISO/I2S1_MCK/SPI3_MISO/I2S3_MCK/USART2_RX/TIM3_CH1/NJTRST_56") (pintype "bidirectional"))
    )
    (net (code "176") (name "unconnected-(IC5-PC6{slash}SPI1_NSS{slash}I2S1_WS{slash}TIM3_CH1-Pad37)") (class "Default")
      (node (ref "IC5") (pin "37") (pinfunction "PC6/SPI1_NSS/I2S1_WS/TIM3_CH1_37") (pintype "bidirectional"))
    )
    (net (code "177") (name "unconnected-(IC5-PC11{slash}SPI3_MISO{slash}I2S3_MCK{slash}USART3_RX-Pad52)") (class "Default")
      (node (ref "IC5") (pin "52") (pinfunction "PC11/SPI3_MISO/I2S3_MCK/USART3_RX_52") (pintype "bidirectional"))
    )
    (net (code "178") (name "unconnected-(IC5-PD2{slash}TIM3_ETR-Pad54)") (class "Default")
      (node (ref "IC5") (pin "54") (pinfunction "PD2/TIM3_ETR_54") (pintype "bidirectional"))
    )
    (net (code "179") (name "unconnected-(IC5-PD8{slash}SPI2_SCK{slash}I2S2_CK{slash}USART3_TX{slash}SDADC3_AIN6P-Pad36)") (class "Default")
      (node (ref "IC5") (pin "36") (pinfunction "PD8/SPI2_SCK/I2S2_CK/USART3_TX/SDADC3_AIN6P_36") (pintype "bidirectional"))
    )
    (net (code "180") (name "unconnected-(IC5-PF6{slash}SPI1_MOSI{slash}I2S1_SD{slash}USART3_RTS{slash}TIM4_CH4{slash}I2C2_SCL-Pad47)") (class "Default")
      (node (ref "IC5") (pin "47") (pinfunction "PF6/SPI1_MOSI/I2S1_SD/USART3_RTS/TIM4_CH4/I2C2_SCL_47") (pintype "bidirectional"))
    )
    (net (code "181") (name "unconnected-(IC5-PF7{slash}I2C2_SDA{slash}USART2_CK-Pad48)") (class "Default")
      (node (ref "IC5") (pin "48") (pinfunction "PF7/I2C2_SDA/USART2_CK_48") (pintype "bidirectional"))
    )
    (net (code "182") (name "unconnected-(IC6A-X5-Pad5)") (class "Default")
      (node (ref "IC6") (pin "5") (pinfunction "X5_5") (pintype "bidirectional"))
    )
    (net (code "183") (name "unconnected-(IC6A-X7-Pad4)") (class "Default")
      (node (ref "IC6") (pin "4") (pinfunction "X7_4") (pintype "bidirectional"))
    )
    (net (code "184") (name "unconnected-(J1-2-PadP2)") (class "Default")
      (node (ref "J1") (pin "P2") (pinfunction "2_P2") (pintype "passive"))
    )
    (net (code "185") (name "unconnected-(J2-2-PadP2)") (class "Default")
      (node (ref "J2") (pin "P2") (pinfunction "2_P2") (pintype "passive"))
    )
    (net (code "186") (name "unconnected-(J3-2-PadP2)") (class "Default")
      (node (ref "J3") (pin "P2") (pinfunction "2_P2") (pintype "passive"))
    )
    (net (code "187") (name "unconnected-(J4-2-PadP2)") (class "Default")
      (node (ref "J4") (pin "P2") (pinfunction "2_P2") (pintype "passive"))
    )
    (net (code "188") (name "unconnected-(J5-2-PadP2)") (class "Default")
      (node (ref "J5") (pin "P2") (pinfunction "2_P2") (pintype "passive"))
    )
    (net (code "189") (name "unconnected-(J6-2-PadP2)") (class "Default")
      (node (ref "J6") (pin "P2") (pinfunction "2_P2") (pintype "passive"))
    )
  )
)
